# Radio_RPIZero.net
KiCad netlist of a schematic drawn in EAGLE
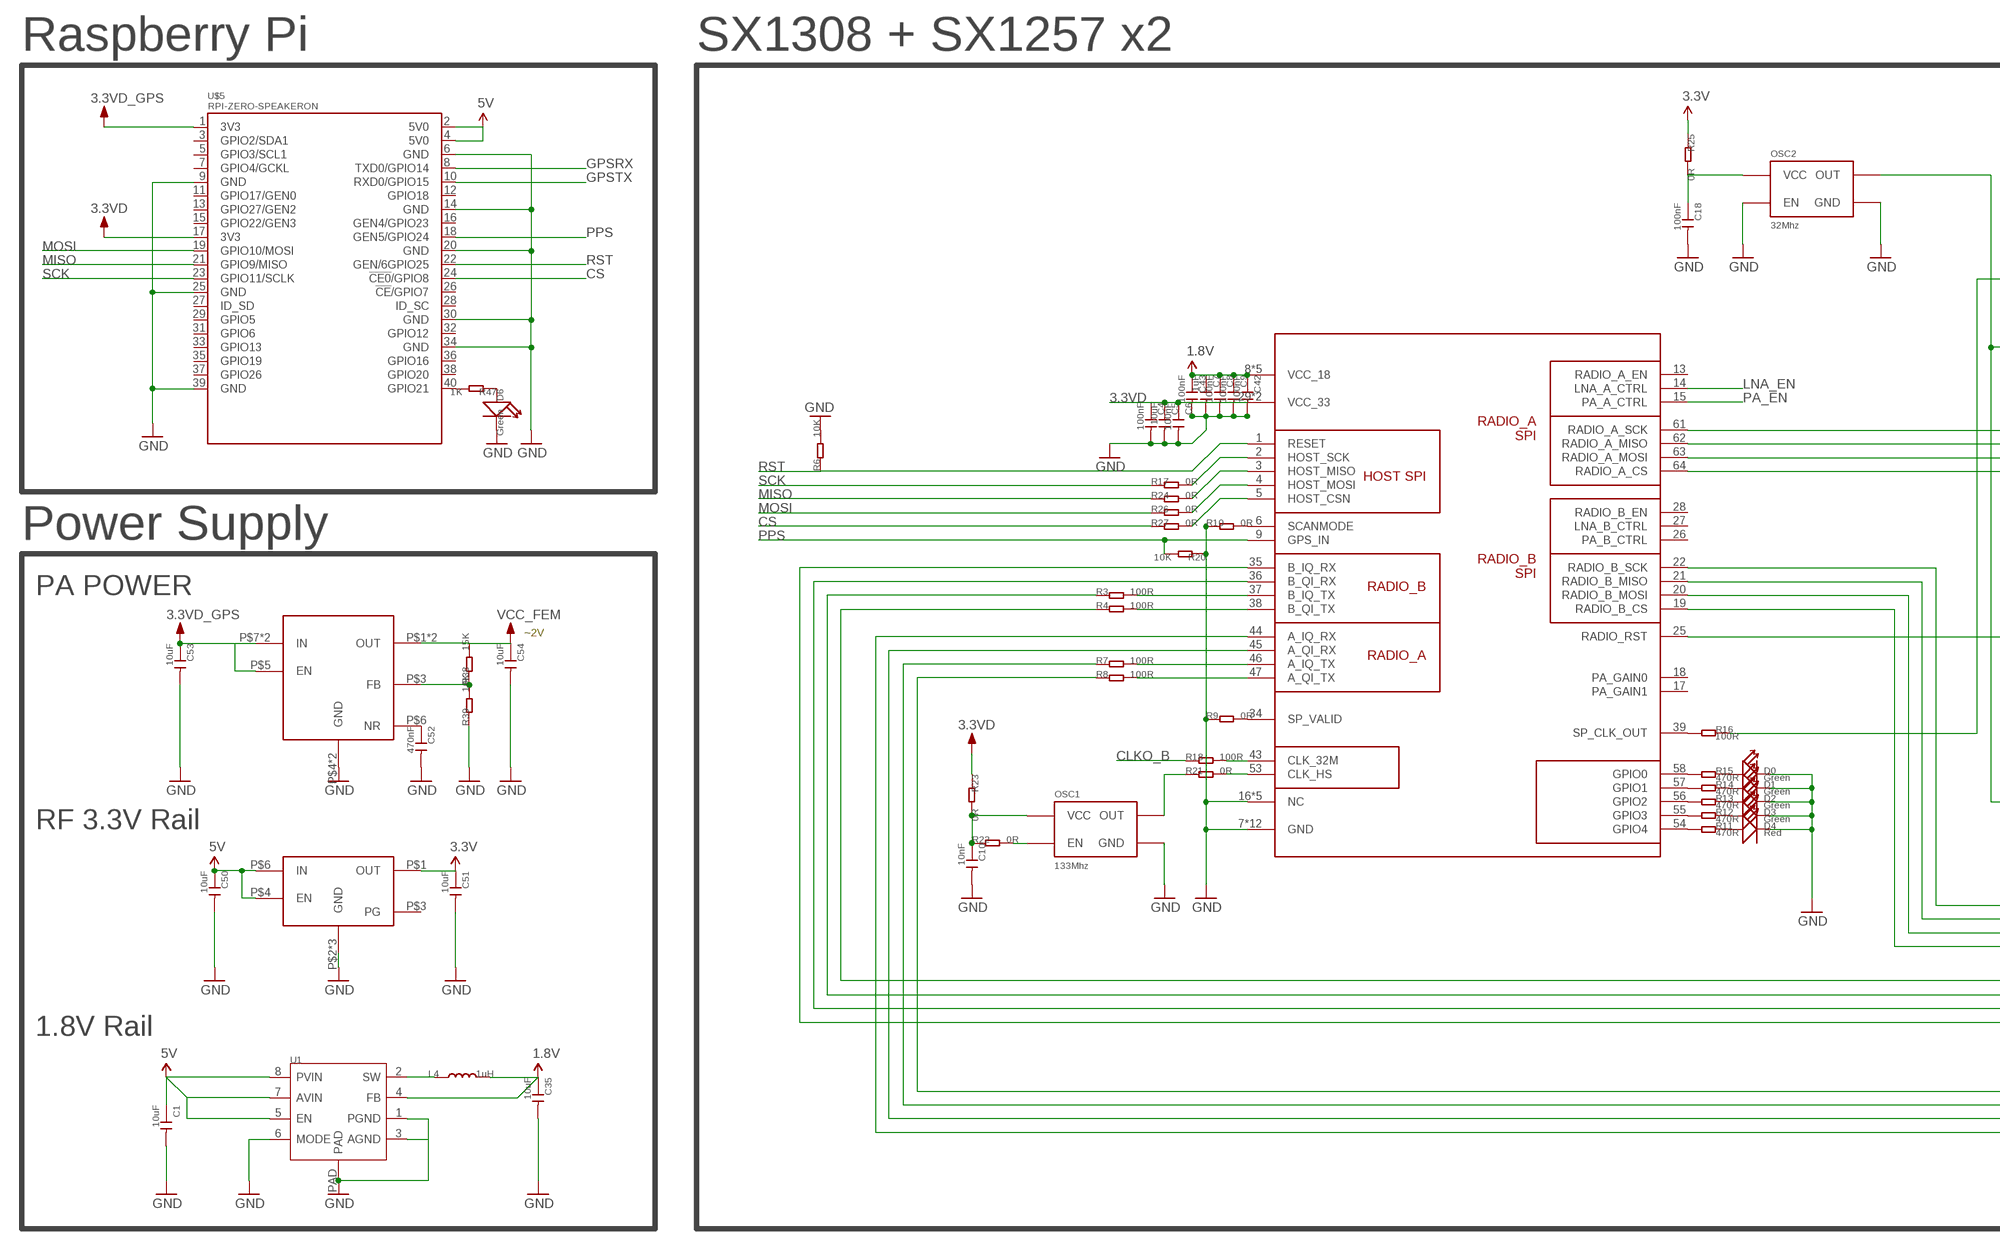
[diagram p0: schematic, sheet 1, part 1 of 2]
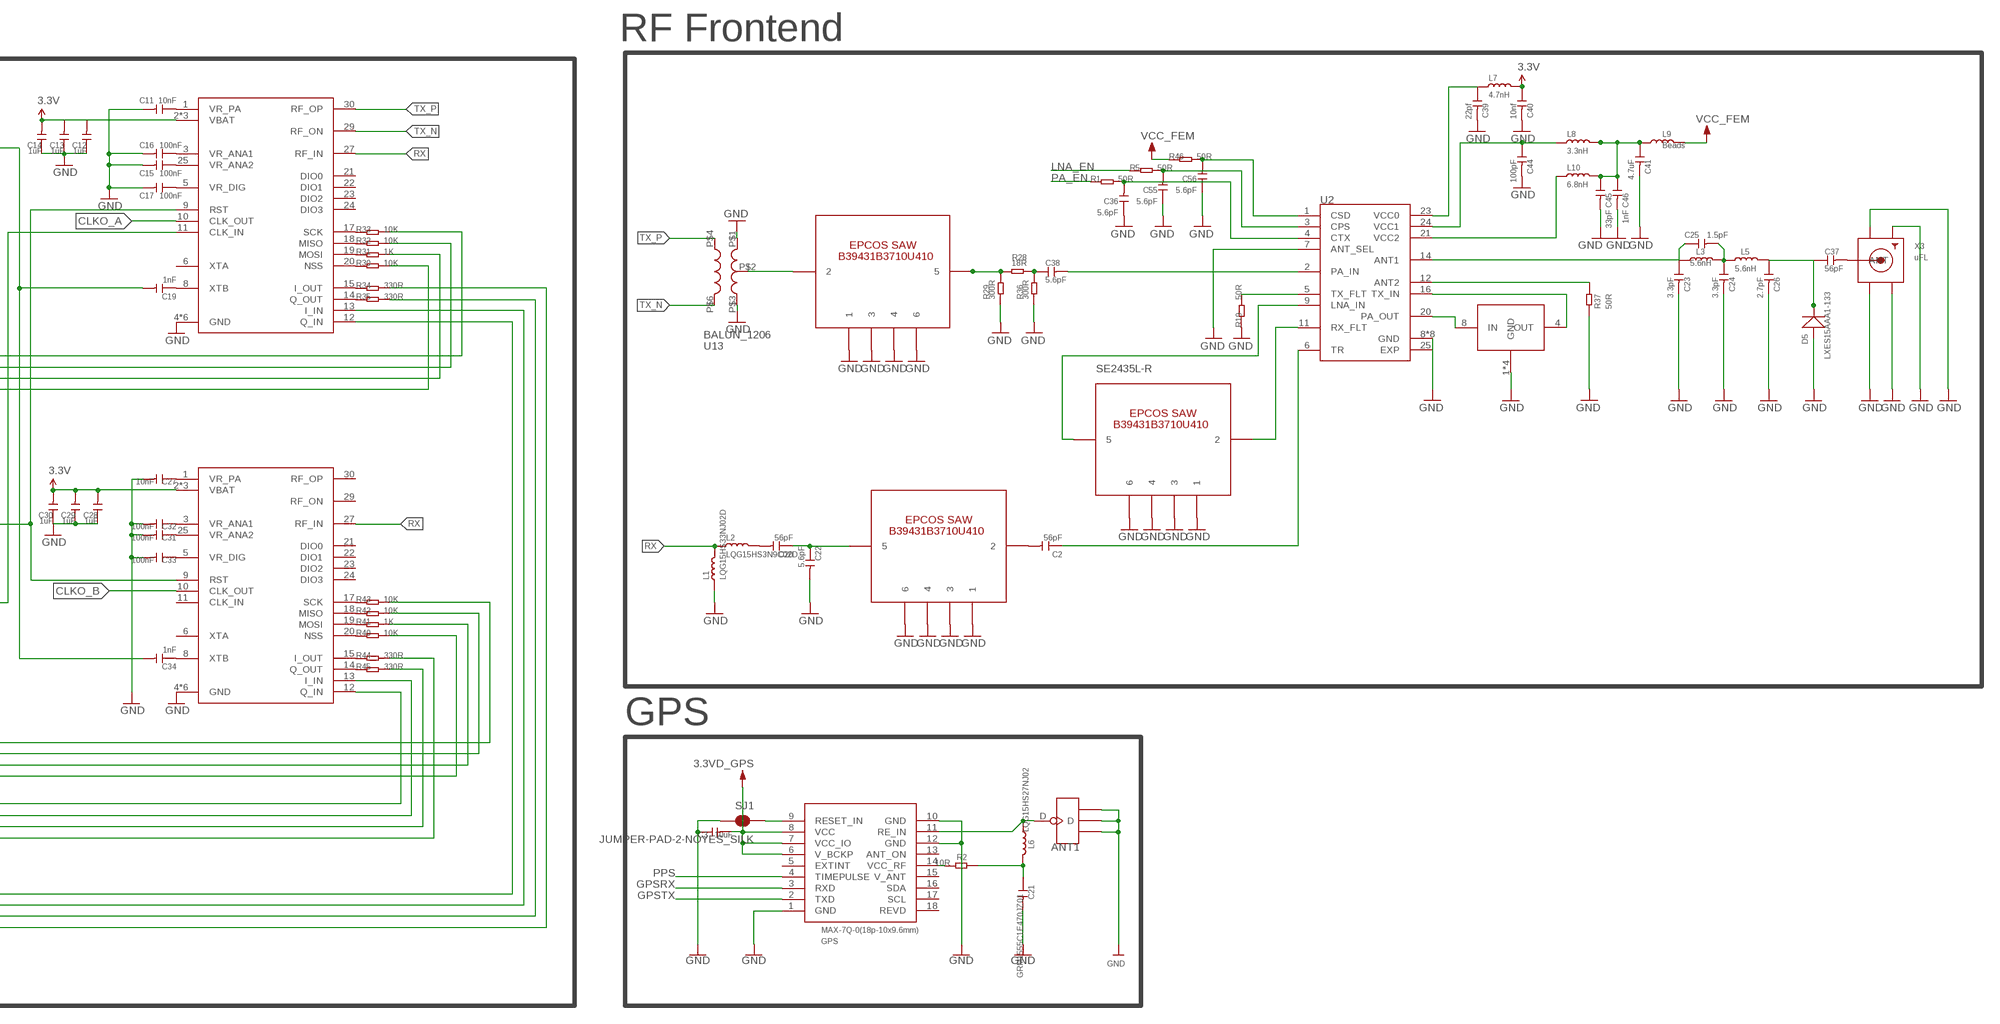
[diagram p1: schematic, sheet 1, part 2 of 2]

(export (version "E")
  (design (tool "Eeschema 10.0.6"))
  (components
    (comp (ref "ANT1")
      (value "ANTENNA-U-FL")
      (footprint "eagle-import:4P-U-FL")
      (libsource (lib "eagle-import") (part "ANTENNA-U-FL"))
    )
    (comp (ref "C1")
      (value "10uF")
      (footprint "eagle-import:C0603@1")
      (libsource (lib "eagle-import") (part "CAP-0603"))
    )
    (comp (ref "C2")
      (value "56pF")
      (footprint "eagle-import:C0402@1")
      (libsource (lib "eagle-import") (part "CAP-0402"))
    )
    (comp (ref "C3")
      (value "10uF")
      (footprint "eagle-import:C0603")
      (libsource (lib "eagle-import") (part "C-0603"))
    )
    (comp (ref "C4")
      (value "100nF")
      (footprint "eagle-import:C0402@1")
      (libsource (lib "eagle-import") (part "CAP-0402"))
    )
    (comp (ref "C5")
      (value "10uF")
      (footprint "eagle-import:C0402@1")
      (libsource (lib "eagle-import") (part "CAP-0402"))
    )
    (comp (ref "C6")
      (value "100nF")
      (footprint "eagle-import:C0402@1")
      (libsource (lib "eagle-import") (part "CAP-0402"))
    )
    (comp (ref "C7")
      (value "1uF")
      (footprint "eagle-import:C0402@1")
      (libsource (lib "eagle-import") (part "CAP-0402"))
    )
    (comp (ref "C8")
      (value "100nF")
      (footprint "eagle-import:C0402@1")
      (libsource (lib "eagle-import") (part "CAP-0402"))
    )
    (comp (ref "C9")
      (value "100nF")
      (footprint "eagle-import:C0402@1")
      (libsource (lib "eagle-import") (part "CAP-0402"))
    )
    (comp (ref "C10")
      (value "10nF")
      (footprint "eagle-import:C0402@1")
      (libsource (lib "eagle-import") (part "CAP-0402"))
    )
    (comp (ref "C11")
      (value "10nF")
      (footprint "eagle-import:C0402@1")
      (libsource (lib "eagle-import") (part "CAP-0402"))
    )
    (comp (ref "C12")
      (value "1uF")
      (footprint "eagle-import:C0402@1")
      (libsource (lib "eagle-import") (part "CAP-0402"))
    )
    (comp (ref "C13")
      (value "1uF")
      (footprint "eagle-import:C0402@1")
      (libsource (lib "eagle-import") (part "CAP-0402"))
    )
    (comp (ref "C14")
      (value "1uF")
      (footprint "eagle-import:C0402@1")
      (libsource (lib "eagle-import") (part "CAP-0402"))
    )
    (comp (ref "C15")
      (value "100nF")
      (footprint "eagle-import:C0402@1")
      (libsource (lib "eagle-import") (part "CAP-0402"))
    )
    (comp (ref "C16")
      (value "100nF")
      (footprint "eagle-import:C0402@1")
      (libsource (lib "eagle-import") (part "CAP-0402"))
    )
    (comp (ref "C17")
      (value "100nF")
      (footprint "eagle-import:C0402@1")
      (libsource (lib "eagle-import") (part "CAP-0402"))
    )
    (comp (ref "C18")
      (value "100nF")
      (footprint "eagle-import:C0402@1")
      (libsource (lib "eagle-import") (part "CAP-0402"))
    )
    (comp (ref "C19")
      (value "1nF")
      (footprint "eagle-import:C0402@1")
      (libsource (lib "eagle-import") (part "CAP-0402"))
    )
    (comp (ref "C20")
      (value "56pF")
      (footprint "eagle-import:C0402@1")
      (libsource (lib "eagle-import") (part "CAP-0402"))
    )
    (comp (ref "C21")
      (value "GRM1555C1E470JZ01")
      (footprint "eagle-import:C0402")
      (libsource (lib "eagle-import") (part "C-0402"))
    )
    (comp (ref "C22")
      (value "5.6pF")
      (footprint "eagle-import:C0402@1")
      (libsource (lib "eagle-import") (part "CAP-0402"))
    )
    (comp (ref "C23")
      (value "3.3pF")
      (footprint "eagle-import:C0402@1")
      (libsource (lib "eagle-import") (part "CAP-0402"))
    )
    (comp (ref "C24")
      (value "3.3pF")
      (footprint "eagle-import:C0402@1")
      (libsource (lib "eagle-import") (part "CAP-0402"))
    )
    (comp (ref "C25")
      (value "1.5pF")
      (footprint "eagle-import:C0402@1")
      (libsource (lib "eagle-import") (part "CAP-0402"))
    )
    (comp (ref "C26")
      (value "2.7pF")
      (footprint "eagle-import:C0402@1")
      (libsource (lib "eagle-import") (part "CAP-0402"))
    )
    (comp (ref "C27")
      (value "10nF")
      (footprint "eagle-import:C0402@1")
      (libsource (lib "eagle-import") (part "CAP-0402"))
    )
    (comp (ref "C28")
      (value "1uF")
      (footprint "eagle-import:C0402@1")
      (libsource (lib "eagle-import") (part "CAP-0402"))
    )
    (comp (ref "C29")
      (value "1uF")
      (footprint "eagle-import:C0402@1")
      (libsource (lib "eagle-import") (part "CAP-0402"))
    )
    (comp (ref "C30")
      (value "1uF")
      (footprint "eagle-import:C0402@1")
      (libsource (lib "eagle-import") (part "CAP-0402"))
    )
    (comp (ref "C31")
      (value "100nF")
      (footprint "eagle-import:C0402@1")
      (libsource (lib "eagle-import") (part "CAP-0402"))
    )
    (comp (ref "C32")
      (value "100nF")
      (footprint "eagle-import:C0402@1")
      (libsource (lib "eagle-import") (part "CAP-0402"))
    )
    (comp (ref "C33")
      (value "100nF")
      (footprint "eagle-import:C0402@1")
      (libsource (lib "eagle-import") (part "CAP-0402"))
    )
    (comp (ref "C34")
      (value "1nF")
      (footprint "eagle-import:C0402@1")
      (libsource (lib "eagle-import") (part "CAP-0402"))
    )
    (comp (ref "C35")
      (value "10uF")
      (footprint "eagle-import:C0603@1")
      (libsource (lib "eagle-import") (part "CAP-0603"))
    )
    (comp (ref "C36")
      (value "5.6pF")
      (footprint "eagle-import:C0402@1")
      (libsource (lib "eagle-import") (part "CAP-0402"))
    )
    (comp (ref "C37")
      (value "56pF")
      (footprint "eagle-import:C0402@1")
      (libsource (lib "eagle-import") (part "CAP-0402"))
    )
    (comp (ref "C38")
      (value "5.6pF")
      (footprint "eagle-import:C0402@1")
      (libsource (lib "eagle-import") (part "CAP-0402"))
    )
    (comp (ref "C39")
      (value "22pf")
      (footprint "eagle-import:C0402@1")
      (libsource (lib "eagle-import") (part "CAP-0402"))
    )
    (comp (ref "C40")
      (value "10nf")
      (footprint "eagle-import:C0402@1")
      (libsource (lib "eagle-import") (part "CAP-0402"))
    )
    (comp (ref "C41")
      (value "4.7uF")
      (footprint "eagle-import:C0402@1")
      (libsource (lib "eagle-import") (part "CAP-0402"))
    )
    (comp (ref "C42")
      (value "100nF")
      (footprint "eagle-import:C0402@1")
      (libsource (lib "eagle-import") (part "CAP-0402"))
    )
    (comp (ref "C43")
      (value "100nF")
      (footprint "eagle-import:C0402@1")
      (libsource (lib "eagle-import") (part "CAP-0402"))
    )
    (comp (ref "C44")
      (value "100pF")
      (footprint "eagle-import:C0402@1")
      (libsource (lib "eagle-import") (part "CAP-0402"))
    )
    (comp (ref "C45")
      (value "33pF")
      (footprint "eagle-import:C0402@1")
      (libsource (lib "eagle-import") (part "CAP-0402"))
    )
    (comp (ref "C46")
      (value "1nF")
      (footprint "eagle-import:C0402@1")
      (libsource (lib "eagle-import") (part "CAP-0402"))
    )
    (comp (ref "C50")
      (value "10uF")
      (footprint "eagle-import:C0603@1")
      (libsource (lib "eagle-import") (part "CAP-0603"))
    )
    (comp (ref "C51")
      (value "10uF")
      (footprint "eagle-import:C0603@1")
      (libsource (lib "eagle-import") (part "CAP-0603"))
    )
    (comp (ref "C52")
      (value "470nF")
      (footprint "eagle-import:C0402@1")
      (libsource (lib "eagle-import") (part "CAP-0402"))
    )
    (comp (ref "C53")
      (value "10uF")
      (footprint "eagle-import:C0402@1")
      (libsource (lib "eagle-import") (part "CAP-0402"))
    )
    (comp (ref "C54")
      (value "10uF")
      (footprint "eagle-import:C0402@1")
      (libsource (lib "eagle-import") (part "CAP-0402"))
    )
    (comp (ref "C55")
      (value "5.6pF")
      (footprint "eagle-import:C0402@1")
      (libsource (lib "eagle-import") (part "CAP-0402"))
    )
    (comp (ref "C56")
      (value "5.6pF")
      (footprint "eagle-import:C0402@1")
      (libsource (lib "eagle-import") (part "CAP-0402"))
    )
    (comp (ref "D0")
      (value "Green")
      (footprint "eagle-import:LED-0603@1")
      (libsource (lib "eagle-import") (part "LED-0603"))
    )
    (comp (ref "D1")
      (value "Green")
      (footprint "eagle-import:LED-0603@1")
      (libsource (lib "eagle-import") (part "LED-0603"))
    )
    (comp (ref "D2")
      (value "Green")
      (footprint "eagle-import:LED-0603@1")
      (libsource (lib "eagle-import") (part "LED-0603"))
    )
    (comp (ref "D3")
      (value "Green")
      (footprint "eagle-import:LED-0603@1")
      (libsource (lib "eagle-import") (part "LED-0603"))
    )
    (comp (ref "D4")
      (value "Red")
      (footprint "eagle-import:LED-0603@1")
      (libsource (lib "eagle-import") (part "LED-0603"))
    )
    (comp (ref "D5")
      (value "LXES15AAA1-133")
      (footprint "eagle-import:C0402")
      (libsource (lib "eagle-import") (part "D"))
    )
    (comp (ref "D6")
      (value "Green")
      (footprint "eagle-import:LED-0603")
      (libsource (lib "eagle-import") (part "LED'0603'"))
    )
    (comp (ref "GPS")
      (value "MAX-7Q-0(18p-10x9.6mm)")
      (footprint "eagle-import:GPS18P-SMD-1.1-10X9.6MM")
      (fields (field (name "MPN") "MAX-7Q-0"))
      (libsource (lib "eagle-import") (part "MODULE-GPS-SMD-MAX-7Q-0(18P-9.6X10MM)"))
    )
    (comp (ref "L1")
      (value "LQG15HS33NJ02D")
      (footprint "eagle-import:L0402@1")
      (libsource (lib "eagle-import") (part "INDUCTOR/FERRITE-BEAD-0402"))
    )
    (comp (ref "L2")
      (value "LQG15HS3N9C02D")
      (footprint "eagle-import:L0402@1")
      (libsource (lib "eagle-import") (part "INDUCTOR/FERRITE-BEAD-0402"))
    )
    (comp (ref "L3")
      (value "5.6nH")
      (footprint "eagle-import:L0402@1")
      (libsource (lib "eagle-import") (part "INDUCTOR/FERRITE-BEAD-0402"))
    )
    (comp (ref "L4")
      (value "1uH")
      (footprint "eagle-import:1616BZ")
      (libsource (lib "eagle-import") (part "L'1616BZ'"))
    )
    (comp (ref "L5")
      (value "5.6nH")
      (footprint "eagle-import:L0402@1")
      (libsource (lib "eagle-import") (part "INDUCTOR/FERRITE-BEAD-0402"))
    )
    (comp (ref "L6")
      (value "LQG15HS27NJ02")
      (footprint "eagle-import:L0402")
      (libsource (lib "eagle-import") (part "L'0402'"))
    )
    (comp (ref "L7")
      (value "4.7nH")
      (footprint "eagle-import:L0402@1")
      (libsource (lib "eagle-import") (part "INDUCTOR/FERRITE-BEAD-0402"))
    )
    (comp (ref "L8")
      (value "3.3nH")
      (footprint "eagle-import:L0402@1")
      (libsource (lib "eagle-import") (part "INDUCTOR/FERRITE-BEAD-0402"))
    )
    (comp (ref "L9")
      (value "Beads")
      (footprint "eagle-import:L0402@1")
      (libsource (lib "eagle-import") (part "INDUCTOR/FERRITE-BEAD-0402"))
    )
    (comp (ref "L10")
      (value "6.8nH")
      (footprint "eagle-import:L0402@1")
      (libsource (lib "eagle-import") (part "INDUCTOR/FERRITE-BEAD-0402"))
    )
    (comp (ref "OSC1")
      (value "133Mhz")
      (footprint "eagle-import:CRYSTAL-OSC-SMD-2.0X2.5")
      (libsource (lib "eagle-import") (part "OSCILLATOR3225"))
    )
    (comp (ref "OSC2")
      (value "32Mhz")
      (footprint "eagle-import:CRYSTAL-OSC-SMD-3.2X2.5")
      (libsource (lib "eagle-import") (part "OSCILLATOR"))
    )
    (comp (ref "R1")
      (value "50R")
      (footprint "eagle-import:R0402")
      (libsource (lib "eagle-import") (part "R-0402"))
    )
    (comp (ref "R2")
      (value "10R")
      (footprint "eagle-import:R0402")
      (libsource (lib "eagle-import") (part "R-0402"))
    )
    (comp (ref "R3")
      (value "100R")
      (footprint "eagle-import:R0402")
      (libsource (lib "eagle-import") (part "R-0402"))
    )
    (comp (ref "R4")
      (value "100R")
      (footprint "eagle-import:R0402")
      (libsource (lib "eagle-import") (part "R-0402"))
    )
    (comp (ref "R5")
      (value "50R")
      (footprint "eagle-import:R0402")
      (libsource (lib "eagle-import") (part "R-0402"))
    )
    (comp (ref "R6")
      (value "10K")
      (footprint "eagle-import:R0402")
      (libsource (lib "eagle-import") (part "R-0402"))
    )
    (comp (ref "R7")
      (value "100R")
      (footprint "eagle-import:R0402")
      (libsource (lib "eagle-import") (part "R-0402"))
    )
    (comp (ref "R8")
      (value "100R")
      (footprint "eagle-import:R0402")
      (libsource (lib "eagle-import") (part "R-0402"))
    )
    (comp (ref "R9")
      (value "0R")
      (footprint "eagle-import:R0402")
      (libsource (lib "eagle-import") (part "R-0402"))
    )
    (comp (ref "R10")
      (value "0R")
      (footprint "eagle-import:R0402")
      (libsource (lib "eagle-import") (part "R-0402"))
    )
    (comp (ref "R11")
      (value "470R")
      (footprint "eagle-import:R0402")
      (libsource (lib "eagle-import") (part "R-0402"))
    )
    (comp (ref "R12")
      (value "470R")
      (footprint "eagle-import:R0402")
      (libsource (lib "eagle-import") (part "R-0402"))
    )
    (comp (ref "R13")
      (value "470R")
      (footprint "eagle-import:R0402")
      (libsource (lib "eagle-import") (part "R-0402"))
    )
    (comp (ref "R14")
      (value "470R")
      (footprint "eagle-import:R0402")
      (libsource (lib "eagle-import") (part "R-0402"))
    )
    (comp (ref "R15")
      (value "470R")
      (footprint "eagle-import:R0402")
      (libsource (lib "eagle-import") (part "R-0402"))
    )
    (comp (ref "R16")
      (value "100R")
      (footprint "eagle-import:R0402")
      (libsource (lib "eagle-import") (part "R-0402"))
    )
    (comp (ref "R17")
      (value "0R")
      (footprint "eagle-import:R0402")
      (libsource (lib "eagle-import") (part "R-0402"))
    )
    (comp (ref "R18")
      (value "100R")
      (footprint "eagle-import:R0402")
      (libsource (lib "eagle-import") (part "R-0402"))
    )
    (comp (ref "R19")
      (value "50R")
      (footprint "eagle-import:R0402")
      (libsource (lib "eagle-import") (part "R-0402"))
    )
    (comp (ref "R20")
      (value "10K")
      (footprint "eagle-import:R0402")
      (libsource (lib "eagle-import") (part "R-0402"))
    )
    (comp (ref "R21")
      (value "0R")
      (footprint "eagle-import:R0402")
      (libsource (lib "eagle-import") (part "R-0402"))
    )
    (comp (ref "R22")
      (value "0R")
      (footprint "eagle-import:R0402")
      (libsource (lib "eagle-import") (part "R-0402"))
    )
    (comp (ref "R23")
      (value "0R")
      (footprint "eagle-import:R0402")
      (libsource (lib "eagle-import") (part "R-0402"))
    )
    (comp (ref "R24")
      (value "0R")
      (footprint "eagle-import:R0402")
      (libsource (lib "eagle-import") (part "R-0402"))
    )
    (comp (ref "R25")
      (value "0R")
      (footprint "eagle-import:R0402")
      (libsource (lib "eagle-import") (part "R-0402"))
    )
    (comp (ref "R26")
      (value "0R")
      (footprint "eagle-import:R0402")
      (libsource (lib "eagle-import") (part "R-0402"))
    )
    (comp (ref "R27")
      (value "0R")
      (footprint "eagle-import:R0402")
      (libsource (lib "eagle-import") (part "R-0402"))
    )
    (comp (ref "R28")
      (value "18R")
      (footprint "eagle-import:R0402")
      (libsource (lib "eagle-import") (part "R-0402"))
    )
    (comp (ref "R29")
      (value "300R")
      (footprint "eagle-import:R0402")
      (libsource (lib "eagle-import") (part "R-0402"))
    )
    (comp (ref "R30")
      (value "10K")
      (footprint "eagle-import:R0402")
      (libsource (lib "eagle-import") (part "R-0402"))
    )
    (comp (ref "R31")
      (value "1K")
      (footprint "eagle-import:R0402")
      (libsource (lib "eagle-import") (part "R-0402"))
    )
    (comp (ref "R32")
      (value "10K")
      (footprint "eagle-import:R0402")
      (libsource (lib "eagle-import") (part "R-0402"))
    )
    (comp (ref "R33")
      (value "10K")
      (footprint "eagle-import:R0402")
      (libsource (lib "eagle-import") (part "R-0402"))
    )
    (comp (ref "R34")
      (value "330R")
      (footprint "eagle-import:R0402")
      (libsource (lib "eagle-import") (part "R-0402"))
    )
    (comp (ref "R35")
      (value "330R")
      (footprint "eagle-import:R0402")
      (libsource (lib "eagle-import") (part "R-0402"))
    )
    (comp (ref "R36")
      (value "300R")
      (footprint "eagle-import:R0402")
      (libsource (lib "eagle-import") (part "R-0402"))
    )
    (comp (ref "R37")
      (value "50R")
      (footprint "eagle-import:R0402")
      (libsource (lib "eagle-import") (part "R-0402"))
    )
    (comp (ref "R38")
      (value "15K")
      (footprint "eagle-import:R0402")
      (libsource (lib "eagle-import") (part "R-0402"))
    )
    (comp (ref "R39")
      (value "10K")
      (footprint "eagle-import:R0402")
      (libsource (lib "eagle-import") (part "R-0402"))
    )
    (comp (ref "R40")
      (value "10K")
      (footprint "eagle-import:R0402")
      (libsource (lib "eagle-import") (part "R-0402"))
    )
    (comp (ref "R41")
      (value "1K")
      (footprint "eagle-import:R0402")
      (libsource (lib "eagle-import") (part "R-0402"))
    )
    (comp (ref "R42")
      (value "10K")
      (footprint "eagle-import:R0402")
      (libsource (lib "eagle-import") (part "R-0402"))
    )
    (comp (ref "R43")
      (value "10K")
      (footprint "eagle-import:R0402")
      (libsource (lib "eagle-import") (part "R-0402"))
    )
    (comp (ref "R44")
      (value "330R")
      (footprint "eagle-import:R0402")
      (libsource (lib "eagle-import") (part "R-0402"))
    )
    (comp (ref "R45")
      (value "330R")
      (footprint "eagle-import:R0402")
      (libsource (lib "eagle-import") (part "R-0402"))
    )
    (comp (ref "R46")
      (value "50R")
      (footprint "eagle-import:R0402")
      (libsource (lib "eagle-import") (part "R-0402"))
    )
    (comp (ref "R47")
      (value "1K")
      (footprint "eagle-import:R0402")
      (libsource (lib "eagle-import") (part "R-0402"))
    )
    (comp (ref "SJ1")
      (value "JUMPER-PAD-2-NOYES_SILK")
      (footprint "eagle-import:PAD-JUMPER-2-NO_YES_SILK")
      (libsource (lib "eagle-import") (part "JUMPER-PAD-2-NOYES_SILK"))
    )
    (comp (ref "U$1")
      (value "SX1301")
      (footprint "eagle-import:QFN64G-0.5-9X9MM")
      (libsource (lib "eagle-import") (part "SX1301"))
    )
    (comp (ref "U$2")
      (value "SX1255")
      (footprint "eagle-import:QFN32G-0.5-5X5MM")
      (libsource (lib "eagle-import") (part "SX1255"))
    )
    (comp (ref "U$3")
      (value "SX1255")
      (footprint "eagle-import:QFN32G-0.5-5X5MM")
      (libsource (lib "eagle-import") (part "SX1255"))
    )
    (comp (ref "U$4")
      (value "B39921B3728U410")
      (footprint "eagle-import:EPCOS_SAW_FILTER")
      (libsource (lib "eagle-import") (part "EPCOS_SAW_FILTER"))
    )
    (comp (ref "U$5")
      (value "RPI-ZERO-SPEAKERON")
      (footprint "eagle-import:RASPBERRYPI_BASTELSTUBE_V13_RASPI_BOARD_B+_FULL")
      (libsource (lib "eagle-import") (part "RPI-ZERO-SPEAKERON"))
    )
    (comp (ref "U$6")
      (value "LP5912")
      (footprint "eagle-import:WSON6")
      (libsource (lib "eagle-import") (part "LP5912"))
    )
    (comp (ref "U$7")
      (value "B39921B3728U410")
      (footprint "eagle-import:EPCOS_SAW_FILTER")
      (libsource (lib "eagle-import") (part "EPCOS_SAW_FILTER"))
    )
    (comp (ref "U$8")
      (value "B39921B3728U410")
      (footprint "eagle-import:EPCOS_SAW_FILTER")
      (libsource (lib "eagle-import") (part "EPCOS_SAW_FILTER"))
    )
    (comp (ref "U$9")
      (value "TPS7A8101")
      (footprint "eagle-import:VSON8")
      (libsource (lib "eagle-import") (part "TPS7A8101"))
    )
    (comp (ref "U$10")
      (value "0915LP15B026")
      (footprint "eagle-import:0915LP15B026")
      (libsource (lib "eagle-import") (part "0915LP15B026"))
    )
    (comp (ref "U1")
      (value "PMIC-ETA3410D2I-T(DFN8-2X2)WSON")
      (footprint "eagle-import:WSON")
      (libsource (lib "eagle-import") (part "PMIC-ETA3410D2I-T(DFN8-2X2)WSON"))
    )
    (comp (ref "U2")
      (value "SE2435L-R")
      (footprint "eagle-import:QFN50P400X400X90-25N")
      (fields (field (name "DIGI-KEY_PART_NUMBER") "863-1349-1-ND") (field (name "MF") "Skyworks Solutions"))
      (libsource (lib "eagle-import") (part "SE2435L-R"))
    )
    (comp (ref "U13")
      (value "BALUN_1206")
      (footprint "eagle-import:BALUN_1206")
      (libsource (lib "eagle-import") (part "BALUN_1206"))
    )
    (comp (ref "X3")
      (value "uFL")
      (footprint "eagle-import:SMA_EDGELAUNCH_UFL")
      (libsource (lib "eagle-import") (part "SMACONNECTOR_EDGE_UFL"))
    )
  )
  (nets
    (net (code "1") (name "/CS") (class "Default")
      (node (ref "R27") (pin "1") (pinfunction "1_1") (pintype "passive"))
      (node (ref "U$5") (pin "24") (pinfunction "~{CE0}/GPIO8_24") (pintype "bidirectional"))
    )
    (net (code "2") (name "/GPSRX") (class "Default")
      (node (ref "GPS") (pin "3") (pinfunction "RXD_3") (pintype "bidirectional"))
      (node (ref "U$5") (pin "8") (pinfunction "TXD0/GPIO14_8") (pintype "bidirectional"))
    )
    (net (code "3") (name "/GPSTX") (class "Default")
      (node (ref "GPS") (pin "2") (pinfunction "TXD_2") (pintype "bidirectional"))
      (node (ref "U$5") (pin "10") (pinfunction "RXD0/GPIO15_10") (pintype "bidirectional"))
    )
    (net (code "4") (name "/LNA_EN") (class "Default")
      (node (ref "R5") (pin "1") (pinfunction "1_1") (pintype "passive"))
      (node (ref "U$1") (pin "14") (pinfunction "LNA_A_CTRL_14") (pintype "bidirectional"))
    )
    (net (code "5") (name "/MISO") (class "Default")
      (node (ref "R24") (pin "1") (pinfunction "1_1") (pintype "passive"))
      (node (ref "U$5") (pin "21") (pinfunction "GPIO9/MISO_21") (pintype "bidirectional"))
    )
    (net (code "6") (name "/MOSI") (class "Default")
      (node (ref "R26") (pin "1") (pinfunction "1_1") (pintype "passive"))
      (node (ref "U$5") (pin "19") (pinfunction "GPIO10/MOSI_19") (pintype "bidirectional"))
    )
    (net (code "7") (name "/PA_EN") (class "Default")
      (node (ref "R1") (pin "1") (pinfunction "1_1") (pintype "passive"))
      (node (ref "U$1") (pin "15") (pinfunction "PA_A_CTRL_15") (pintype "bidirectional"))
    )
    (net (code "8") (name "/PPS") (class "Default")
      (node (ref "GPS") (pin "4") (pinfunction "TIMEPULSE_4") (pintype "bidirectional"))
      (node (ref "R20") (pin "2") (pinfunction "2_2") (pintype "passive"))
      (node (ref "U$1") (pin "9") (pinfunction "GPS_IN_9") (pintype "bidirectional"))
      (node (ref "U$5") (pin "18") (pinfunction "GEN5/GPIO24_18") (pintype "bidirectional"))
    )
    (net (code "9") (name "/RST") (class "Default")
      (node (ref "R6") (pin "1") (pinfunction "1_1") (pintype "passive"))
      (node (ref "U$1") (pin "1") (pinfunction "RESET_1") (pintype "bidirectional"))
      (node (ref "U$5") (pin "22") (pinfunction "GEN/6GPIO25_22") (pintype "bidirectional"))
    )
    (net (code "10") (name "/SCK") (class "Default")
      (node (ref "R17") (pin "1") (pinfunction "1_1") (pintype "passive"))
      (node (ref "U$5") (pin "23") (pinfunction "GPIO11/SCLK_23") (pintype "bidirectional"))
    )
    (net (code "11") (name "1.8V") (class "Default")
      (node (ref "C35") (pin "1") (pinfunction "1_1") (pintype "passive"))
      (node (ref "C42") (pin "1") (pinfunction "1_1") (pintype "passive"))
      (node (ref "C43") (pin "1") (pinfunction "1_1") (pintype "passive"))
      (node (ref "C7") (pin "1") (pinfunction "1_1") (pintype "passive"))
      (node (ref "C8") (pin "1") (pinfunction "1_1") (pintype "passive"))
      (node (ref "C9") (pin "1") (pinfunction "1_1") (pintype "passive"))
      (node (ref "L4") (pin "2") (pinfunction "2_2") (pintype "passive"))
      (node (ref "U$1") (pin "12") (pinfunction "VCC_18_12") (pintype "bidirectional"))
      (node (ref "U$1") (pin "23") (pinfunction "VCC_18_23") (pintype "bidirectional"))
      (node (ref "U$1") (pin "42") (pinfunction "VCC_18_42") (pintype "bidirectional"))
      (node (ref "U$1") (pin "60") (pinfunction "VCC_18_60") (pintype "bidirectional"))
      (node (ref "U$1") (pin "8") (pinfunction "VCC_18_8") (pintype "bidirectional"))
      (node (ref "U1") (pin "4") (pinfunction "FB_4") (pintype "bidirectional"))
    )
    (net (code "12") (name "3.3V") (class "Default")
      (node (ref "C12") (pin "2") (pinfunction "2_2") (pintype "passive"))
      (node (ref "C13") (pin "2") (pinfunction "2_2") (pintype "passive"))
      (node (ref "C14") (pin "2") (pinfunction "2_2") (pintype "passive"))
      (node (ref "C28") (pin "2") (pinfunction "2_2") (pintype "passive"))
      (node (ref "C29") (pin "2") (pinfunction "2_2") (pintype "passive"))
      (node (ref "C30") (pin "2") (pinfunction "2_2") (pintype "passive"))
      (node (ref "C40") (pin "1") (pinfunction "1_1") (pintype "passive"))
      (node (ref "C51") (pin "1") (pinfunction "1_1") (pintype "passive"))
      (node (ref "L7") (pin "2") (pinfunction "2_2") (pintype "passive"))
      (node (ref "R25") (pin "1") (pinfunction "1_1") (pintype "passive"))
      (node (ref "U$2") (pin "16") (pinfunction "VBAT_16") (pintype "bidirectional"))
      (node (ref "U$2") (pin "2") (pinfunction "VBAT_2") (pintype "bidirectional"))
      (node (ref "U$2") (pin "32") (pinfunction "VBAT_32") (pintype "bidirectional"))
      (node (ref "U$3") (pin "16") (pinfunction "VBAT_16") (pintype "bidirectional"))
      (node (ref "U$3") (pin "2") (pinfunction "VBAT_2") (pintype "bidirectional"))
      (node (ref "U$3") (pin "32") (pinfunction "VBAT_32") (pintype "bidirectional"))
      (node (ref "U$6") (pin "P$1") (pinfunction "OUT_P$1") (pintype "bidirectional"))
    )
    (net (code "13") (name "3.3VD") (class "Default")
      (node (ref "C4") (pin "1") (pinfunction "1_1") (pintype "passive"))
      (node (ref "C5") (pin "1") (pinfunction "1_1") (pintype "passive"))
      (node (ref "C6") (pin "1") (pinfunction "1_1") (pintype "passive"))
      (node (ref "R23") (pin "1") (pinfunction "1_1") (pintype "passive"))
      (node (ref "U$1") (pin "29") (pinfunction "VCC_33_29") (pintype "bidirectional"))
      (node (ref "U$1") (pin "52") (pinfunction "VCC_33_52") (pintype "bidirectional"))
      (node (ref "U$5") (pin "17") (pinfunction "3V3_17") (pintype "power_in"))
    )
    (net (code "14") (name "3.3VD_GPS") (class "Default")
      (node (ref "C3") (pin "2") (pinfunction "2_2") (pintype "passive"))
      (node (ref "C53") (pin "1") (pinfunction "1_1") (pintype "passive"))
      (node (ref "GPS") (pin "6") (pinfunction "V_BCKP_6") (pintype "bidirectional"))
      (node (ref "GPS") (pin "7") (pinfunction "VCC_IO_7") (pintype "bidirectional"))
      (node (ref "GPS") (pin "8") (pinfunction "VCC_8") (pintype "bidirectional"))
      (node (ref "U$5") (pin "1") (pinfunction "3V3_1") (pintype "power_in"))
      (node (ref "U$9") (pin "P$5") (pinfunction "EN_P$5") (pintype "bidirectional"))
      (node (ref "U$9") (pin "P$7") (pinfunction "IN_P$7") (pintype "bidirectional"))
      (node (ref "U$9") (pin "P$8") (pinfunction "IN_P$8") (pintype "bidirectional"))
    )
    (net (code "15") (name "5V") (class "Default")
      (node (ref "C1") (pin "1") (pinfunction "1_1") (pintype "passive"))
      (node (ref "C50") (pin "1") (pinfunction "1_1") (pintype "passive"))
      (node (ref "U$5") (pin "2") (pinfunction "5V0_2") (pintype "power_in"))
      (node (ref "U$5") (pin "4") (pinfunction "5V0_4") (pintype "power_in"))
      (node (ref "U$6") (pin "P$4") (pinfunction "EN_P$4") (pintype "bidirectional"))
      (node (ref "U$6") (pin "P$6") (pinfunction "IN_P$6") (pintype "bidirectional"))
      (node (ref "U1") (pin "5") (pinfunction "EN_5") (pintype "bidirectional"))
      (node (ref "U1") (pin "7") (pinfunction "AVIN_7") (pintype "bidirectional"))
      (node (ref "U1") (pin "8") (pinfunction "PVIN_8") (pintype "bidirectional"))
    )
    (net (code "16") (name "CLKO_A") (class "Default")
      (node (ref "U$2") (pin "10") (pinfunction "CLK_OUT_10") (pintype "bidirectional"))
    )
    (net (code "17") (name "CLKO_B") (class "Default")
      (node (ref "R18") (pin "1") (pinfunction "1_1") (pintype "passive"))
      (node (ref "U$3") (pin "10") (pinfunction "CLK_OUT_10") (pintype "bidirectional"))
    )
    (net (code "18") (name "GND") (class "Default")
      (node (ref "ANT1") (pin "GND1") (pinfunction "GND1_GND1") (pintype "bidirectional"))
      (node (ref "ANT1") (pin "GND2") (pinfunction "GND2_GND2") (pintype "bidirectional"))
      (node (ref "ANT1") (pin "GND3") (pinfunction "GND3_GND3") (pintype "bidirectional"))
      (node (ref "C1") (pin "2") (pinfunction "2_2") (pintype "passive"))
      (node (ref "C10") (pin "2") (pinfunction "2_2") (pintype "passive"))
      (node (ref "C11") (pin "2") (pinfunction "2_2") (pintype "passive"))
      (node (ref "C12") (pin "1") (pinfunction "1_1") (pintype "passive"))
      (node (ref "C13") (pin "1") (pinfunction "1_1") (pintype "passive"))
      (node (ref "C14") (pin "1") (pinfunction "1_1") (pintype "passive"))
      (node (ref "C15") (pin "2") (pinfunction "2_2") (pintype "passive"))
      (node (ref "C16") (pin "2") (pinfunction "2_2") (pintype "passive"))
      (node (ref "C17") (pin "2") (pinfunction "2_2") (pintype "passive"))
      (node (ref "C18") (pin "2") (pinfunction "2_2") (pintype "passive"))
      (node (ref "C21") (pin "2") (pinfunction "2_2") (pintype "passive"))
      (node (ref "C22") (pin "2") (pinfunction "2_2") (pintype "passive"))
      (node (ref "C23") (pin "2") (pinfunction "2_2") (pintype "passive"))
      (node (ref "C24") (pin "2") (pinfunction "2_2") (pintype "passive"))
      (node (ref "C26") (pin "2") (pinfunction "2_2") (pintype "passive"))
      (node (ref "C27") (pin "2") (pinfunction "2_2") (pintype "passive"))
      (node (ref "C28") (pin "1") (pinfunction "1_1") (pintype "passive"))
      (node (ref "C29") (pin "1") (pinfunction "1_1") (pintype "passive"))
      (node (ref "C3") (pin "1") (pinfunction "1_1") (pintype "passive"))
      (node (ref "C30") (pin "1") (pinfunction "1_1") (pintype "passive"))
      (node (ref "C31") (pin "2") (pinfunction "2_2") (pintype "passive"))
      (node (ref "C32") (pin "2") (pinfunction "2_2") (pintype "passive"))
      (node (ref "C33") (pin "2") (pinfunction "2_2") (pintype "passive"))
      (node (ref "C35") (pin "2") (pinfunction "2_2") (pintype "passive"))
      (node (ref "C36") (pin "1") (pinfunction "1_1") (pintype "passive"))
      (node (ref "C39") (pin "2") (pinfunction "2_2") (pintype "passive"))
      (node (ref "C4") (pin "2") (pinfunction "2_2") (pintype "passive"))
      (node (ref "C40") (pin "2") (pinfunction "2_2") (pintype "passive"))
      (node (ref "C41") (pin "2") (pinfunction "2_2") (pintype "passive"))
      (node (ref "C42") (pin "2") (pinfunction "2_2") (pintype "passive"))
      (node (ref "C43") (pin "2") (pinfunction "2_2") (pintype "passive"))
      (node (ref "C44") (pin "2") (pinfunction "2_2") (pintype "passive"))
      (node (ref "C45") (pin "2") (pinfunction "2_2") (pintype "passive"))
      (node (ref "C46") (pin "2") (pinfunction "2_2") (pintype "passive"))
      (node (ref "C5") (pin "2") (pinfunction "2_2") (pintype "passive"))
      (node (ref "C50") (pin "2") (pinfunction "2_2") (pintype "passive"))
      (node (ref "C51") (pin "2") (pinfunction "2_2") (pintype "passive"))
      (node (ref "C52") (pin "2") (pinfunction "2_2") (pintype "passive"))
      (node (ref "C53") (pin "2") (pinfunction "2_2") (pintype "passive"))
      (node (ref "C54") (pin "2") (pinfunction "2_2") (pintype "passive"))
      (node (ref "C55") (pin "1") (pinfunction "1_1") (pintype "passive"))
      (node (ref "C56") (pin "1") (pinfunction "1_1") (pintype "passive"))
      (node (ref "C6") (pin "2") (pinfunction "2_2") (pintype "passive"))
      (node (ref "C7") (pin "2") (pinfunction "2_2") (pintype "passive"))
      (node (ref "C8") (pin "2") (pinfunction "2_2") (pintype "passive"))
      (node (ref "C9") (pin "2") (pinfunction "2_2") (pintype "passive"))
      (node (ref "D0") (pin "-") (pinfunction "-_-") (pintype "passive"))
      (node (ref "D1") (pin "-") (pinfunction "-_-") (pintype "passive"))
      (node (ref "D2") (pin "-") (pinfunction "-_-") (pintype "passive"))
      (node (ref "D3") (pin "-") (pinfunction "-_-") (pintype "passive"))
      (node (ref "D4") (pin "-") (pinfunction "-_-") (pintype "passive"))
      (node (ref "D5") (pin "1") (pinfunction "+_1") (pintype "passive"))
      (node (ref "D6") (pin "-") (pinfunction "-_-") (pintype "passive"))
      (node (ref "GPS") (pin "1") (pinfunction "GND_1") (pintype "bidirectional"))
      (node (ref "GPS") (pin "10") (pinfunction "GND_10") (pintype "bidirectional"))
      (node (ref "GPS") (pin "12") (pinfunction "GND_12") (pintype "bidirectional"))
      (node (ref "L1") (pin "1") (pinfunction "1_1") (pintype "passive"))
      (node (ref "OSC1") (pin "2") (pinfunction "GND_2") (pintype "bidirectional"))
      (node (ref "OSC2") (pin "P$1") (pinfunction "EN_P$1") (pintype "bidirectional"))
      (node (ref "OSC2") (pin "P$2") (pinfunction "GND_P$2") (pintype "bidirectional"))
      (node (ref "R10") (pin "1") (pinfunction "1_1") (pintype "passive"))
      (node (ref "R19") (pin "1") (pinfunction "1_1") (pintype "passive"))
      (node (ref "R20") (pin "1") (pinfunction "1_1") (pintype "passive"))
      (node (ref "R29") (pin "1") (pinfunction "1_1") (pintype "passive"))
      (node (ref "R36") (pin "1") (pinfunction "1_1") (pintype "passive"))
      (node (ref "R37") (pin "2") (pinfunction "2_2") (pintype "passive"))
      (node (ref "R39") (pin "1") (pinfunction "1_1") (pintype "passive"))
      (node (ref "R6") (pin "2") (pinfunction "2_2") (pintype "passive"))
      (node (ref "R9") (pin "1") (pinfunction "1_1") (pintype "passive"))
      (node (ref "SJ1") (pin "2") (pinfunction "2_2") (pintype "passive"))
      (node (ref "U$1") (pin "10") (pinfunction "GND_10") (pintype "bidirectional"))
      (node (ref "U$1") (pin "11") (pinfunction "GND_11") (pintype "bidirectional"))
      (node (ref "U$1") (pin "16") (pinfunction "NC_16") (pintype "bidirectional"))
      (node (ref "U$1") (pin "24") (pinfunction "GND_24") (pintype "bidirectional"))
      (node (ref "U$1") (pin "30") (pinfunction "GND_30") (pintype "bidirectional"))
      (node (ref "U$1") (pin "31") (pinfunction "GND_31") (pintype "bidirectional"))
      (node (ref "U$1") (pin "32") (pinfunction "NC_32") (pintype "bidirectional"))
      (node (ref "U$1") (pin "33") (pinfunction "NC_33") (pintype "bidirectional"))
      (node (ref "U$1") (pin "40") (pinfunction "GND_40") (pintype "bidirectional"))
      (node (ref "U$1") (pin "41") (pinfunction "GND_41") (pintype "bidirectional"))
      (node (ref "U$1") (pin "48") (pinfunction "NC_48") (pintype "bidirectional"))
      (node (ref "U$1") (pin "49") (pinfunction "NC_49") (pintype "bidirectional"))
      (node (ref "U$1") (pin "50") (pinfunction "GND_50") (pintype "bidirectional"))
      (node (ref "U$1") (pin "51") (pinfunction "GND_51") (pintype "bidirectional"))
      (node (ref "U$1") (pin "59") (pinfunction "GND_59") (pintype "bidirectional"))
      (node (ref "U$1") (pin "65") (pinfunction "GND_65") (pintype "bidirectional"))
      (node (ref "U$1") (pin "7") (pinfunction "GND_7") (pintype "bidirectional"))
      (node (ref "U$10") (pin "1") (pinfunction "GND_1") (pintype "bidirectional"))
      (node (ref "U$10") (pin "3") (pinfunction "GND_3") (pintype "bidirectional"))
      (node (ref "U$10") (pin "5") (pinfunction "GND_5") (pintype "bidirectional"))
      (node (ref "U$10") (pin "7") (pinfunction "GND_7") (pintype "bidirectional"))
      (node (ref "U$2") (pin "26") (pinfunction "GND_26") (pintype "bidirectional"))
      (node (ref "U$2") (pin "28") (pinfunction "GND_28") (pintype "bidirectional"))
      (node (ref "U$2") (pin "31") (pinfunction "GND_31") (pintype "bidirectional"))
      (node (ref "U$2") (pin "33") (pinfunction "GND_33") (pintype "bidirectional"))
      (node (ref "U$2") (pin "4") (pinfunction "GND_4") (pintype "bidirectional"))
      (node (ref "U$2") (pin "7") (pinfunction "GND_7") (pintype "bidirectional"))
      (node (ref "U$3") (pin "26") (pinfunction "GND_26") (pintype "bidirectional"))
      (node (ref "U$3") (pin "28") (pinfunction "GND_28") (pintype "bidirectional"))
      (node (ref "U$3") (pin "31") (pinfunction "GND_31") (pintype "bidirectional"))
      (node (ref "U$3") (pin "33") (pinfunction "GND_33") (pintype "bidirectional"))
      (node (ref "U$3") (pin "4") (pinfunction "GND_4") (pintype "bidirectional"))
      (node (ref "U$3") (pin "7") (pinfunction "GND_7") (pintype "bidirectional"))
      (node (ref "U$4") (pin "P$1") (pinfunction "1_P$1") (pintype "bidirectional"))
      (node (ref "U$4") (pin "P$3") (pinfunction "3_P$3") (pintype "bidirectional"))
      (node (ref "U$4") (pin "P$4") (pinfunction "4_P$4") (pintype "bidirectional"))
      (node (ref "U$4") (pin "P$6") (pinfunction "6_P$6") (pintype "bidirectional"))
      (node (ref "U$5") (pin "14") (pinfunction "GND_14") (pintype "power_in"))
      (node (ref "U$5") (pin "20") (pinfunction "GND_20") (pintype "power_in"))
      (node (ref "U$5") (pin "25") (pinfunction "GND_25") (pintype "power_in"))
      (node (ref "U$5") (pin "30") (pinfunction "GND_30") (pintype "power_in"))
      (node (ref "U$5") (pin "34") (pinfunction "GND_34") (pintype "power_in"))
      (node (ref "U$5") (pin "39") (pinfunction "GND_39") (pintype "power_in"))
      (node (ref "U$5") (pin "6") (pinfunction "GND_6") (pintype "power_in"))
      (node (ref "U$5") (pin "9") (pinfunction "GND_9") (pintype "power_in"))
      (node (ref "U$6") (pin "P$2") (pinfunction "GND_P$2") (pintype "bidirectional"))
      (node (ref "U$6") (pin "P$5") (pinfunction "GND_P$5") (pintype "bidirectional"))
      (node (ref "U$6") (pin "PAD") (pinfunction "GND_PAD") (pintype "bidirectional"))
      (node (ref "U$7") (pin "P$1") (pinfunction "1_P$1") (pintype "bidirectional"))
      (node (ref "U$7") (pin "P$3") (pinfunction "3_P$3") (pintype "bidirectional"))
      (node (ref "U$7") (pin "P$4") (pinfunction "4_P$4") (pintype "bidirectional"))
      (node (ref "U$7") (pin "P$6") (pinfunction "6_P$6") (pintype "bidirectional"))
      (node (ref "U$8") (pin "P$1") (pinfunction "1_P$1") (pintype "bidirectional"))
      (node (ref "U$8") (pin "P$3") (pinfunction "3_P$3") (pintype "bidirectional"))
      (node (ref "U$8") (pin "P$4") (pinfunction "4_P$4") (pintype "bidirectional"))
      (node (ref "U$8") (pin "P$6") (pinfunction "6_P$6") (pintype "bidirectional"))
      (node (ref "U$9") (pin "P$4") (pinfunction "GND_P$4") (pintype "bidirectional"))
      (node (ref "U$9") (pin "PAD") (pinfunction "GND_PAD") (pintype "bidirectional"))
      (node (ref "U1") (pin "1") (pinfunction "PGND_1") (pintype "bidirectional"))
      (node (ref "U1") (pin "3") (pinfunction "AGND_3") (pintype "bidirectional"))
      (node (ref "U1") (pin "6") (pinfunction "MODE_6") (pintype "bidirectional"))
      (node (ref "U1") (pin "PAD") (pinfunction "PAD_PAD") (pintype "bidirectional"))
      (node (ref "U13") (pin "P$1") (pinfunction "GND_1_P$1") (pintype "bidirectional"))
      (node (ref "U13") (pin "P$3") (pinfunction "GND_2_P$3") (pintype "bidirectional"))
      (node (ref "U2") (pin "10") (pinfunction "GND_10") (pintype "power_in"))
      (node (ref "U2") (pin "13") (pinfunction "GND_13") (pintype "power_in"))
      (node (ref "U2") (pin "15") (pinfunction "GND_15") (pintype "power_in"))
      (node (ref "U2") (pin "17") (pinfunction "GND_17") (pintype "power_in"))
      (node (ref "U2") (pin "18") (pinfunction "GND_18") (pintype "power_in"))
      (node (ref "U2") (pin "19") (pinfunction "GND_19") (pintype "power_in"))
      (node (ref "U2") (pin "22") (pinfunction "GND_22") (pintype "power_in"))
      (node (ref "U2") (pin "25") (pinfunction "EXP_25") (pintype "power_in"))
      (node (ref "U2") (pin "7") (pinfunction "ANT_SEL_7") (pintype "input"))
      (node (ref "U2") (pin "8") (pinfunction "GND_8") (pintype "power_in"))
      (node (ref "X3") (pin "GND@1") (pinfunction "GND1_GND@1") (pintype "power_in"))
      (node (ref "X3") (pin "GND@2") (pinfunction "GND2_GND@2") (pintype "power_in"))
      (node (ref "X3") (pin "GND@3") (pinfunction "GND3_GND@3") (pintype "power_in"))
      (node (ref "X3") (pin "GND@4") (pinfunction "GND4_GND@4") (pintype "power_in"))
    )
    (net (code "19") (name "Net-(C20-Pad2)") (class "Default")
      (node (ref "C20") (pin "2") (pinfunction "2_2") (pintype "passive"))
      (node (ref "L2") (pin "2") (pinfunction "2_2") (pintype "passive"))
    )
    (net (code "20") (name "Net-(C21-Pad1)") (class "Default")
      (node (ref "C21") (pin "1") (pinfunction "1_1") (pintype "passive"))
      (node (ref "L6") (pin "1") (pinfunction "1_1") (pintype "passive"))
      (node (ref "R2") (pin "1") (pinfunction "1_1") (pintype "passive"))
    )
    (net (code "21") (name "Net-(C24-Pad1)") (class "Default")
      (node (ref "C24") (pin "1") (pinfunction "1_1") (pintype "passive"))
      (node (ref "C25") (pin "2") (pinfunction "2_2") (pintype "passive"))
      (node (ref "L3") (pin "2") (pinfunction "2_2") (pintype "passive"))
      (node (ref "L5") (pin "1") (pinfunction "1_1") (pintype "passive"))
    )
    (net (code "22") (name "Net-(C38-Pad1)") (class "Default")
      (node (ref "C38") (pin "1") (pinfunction "1_1") (pintype "passive"))
      (node (ref "R28") (pin "2") (pinfunction "2_2") (pintype "passive"))
      (node (ref "R36") (pin "2") (pinfunction "2_2") (pintype "passive"))
    )
    (net (code "23") (name "Net-(C41-Pad1)") (class "Default")
      (node (ref "C41") (pin "1") (pinfunction "1_1") (pintype "passive"))
      (node (ref "C45") (pin "1") (pinfunction "1_1") (pintype "passive"))
      (node (ref "C46") (pin "1") (pinfunction "1_1") (pintype "passive"))
      (node (ref "L10") (pin "2") (pinfunction "2_2") (pintype "passive"))
      (node (ref "L8") (pin "2") (pinfunction "2_2") (pintype "passive"))
      (node (ref "L9") (pin "1") (pinfunction "1_1") (pintype "passive"))
    )
    (net (code "24") (name "Net-(D0-Pad+)") (class "Default")
      (node (ref "D0") (pin "+") (pinfunction "+_+") (pintype "passive"))
      (node (ref "R15") (pin "2") (pinfunction "2_2") (pintype "passive"))
    )
    (net (code "25") (name "Net-(D1-Pad+)") (class "Default")
      (node (ref "D1") (pin "+") (pinfunction "+_+") (pintype "passive"))
      (node (ref "R14") (pin "2") (pinfunction "2_2") (pintype "passive"))
    )
    (net (code "26") (name "Net-(D2-Pad+)") (class "Default")
      (node (ref "D2") (pin "+") (pinfunction "+_+") (pintype "passive"))
      (node (ref "R13") (pin "2") (pinfunction "2_2") (pintype "passive"))
    )
    (net (code "27") (name "Net-(D3-Pad+)") (class "Default")
      (node (ref "D3") (pin "+") (pinfunction "+_+") (pintype "passive"))
      (node (ref "R12") (pin "2") (pinfunction "2_2") (pintype "passive"))
    )
    (net (code "28") (name "Net-(D4-Pad+)") (class "Default")
      (node (ref "D4") (pin "+") (pinfunction "+_+") (pintype "passive"))
      (node (ref "R11") (pin "2") (pinfunction "2_2") (pintype "passive"))
    )
    (net (code "29") (name "Net-(D5--)") (class "Default")
      (node (ref "C26") (pin "1") (pinfunction "1_1") (pintype "passive"))
      (node (ref "C37") (pin "1") (pinfunction "1_1") (pintype "passive"))
      (node (ref "D5") (pin "2") (pinfunction "-_2") (pintype "passive"))
      (node (ref "L5") (pin "2") (pinfunction "2_2") (pintype "passive"))
    )
    (net (code "30") (name "Net-(D6-Pad+)") (class "Default")
      (node (ref "D6") (pin "+") (pinfunction "+_+") (pintype "passive"))
      (node (ref "R47") (pin "1") (pinfunction "1_1") (pintype "passive"))
    )
    (net (code "31") (name "Net-(GPS-RESET_IN)") (class "Default")
      (node (ref "GPS") (pin "9") (pinfunction "RESET_IN_9") (pintype "bidirectional"))
      (node (ref "SJ1") (pin "1") (pinfunction "1_1") (pintype "passive"))
    )
    (net (code "32") (name "Net-(GPS-RE_IN)") (class "Default")
      (node (ref "ANT1") (pin "D") (pinfunction "D_D") (pintype "bidirectional"))
      (node (ref "GPS") (pin "11") (pinfunction "RE_IN_11") (pintype "bidirectional"))
      (node (ref "L6") (pin "2") (pinfunction "2_2") (pintype "passive"))
    )
    (net (code "33") (name "Net-(GPS-VCC_RF)") (class "Default")
      (node (ref "GPS") (pin "14") (pinfunction "VCC_RF_14") (pintype "bidirectional"))
      (node (ref "R2") (pin "2") (pinfunction "2_2") (pintype "passive"))
    )
    (net (code "34") (name "Net-(OSC1-EN)") (class "Default")
      (node (ref "OSC1") (pin "1") (pinfunction "EN_1") (pintype "bidirectional"))
      (node (ref "R22") (pin "2") (pinfunction "2_2") (pintype "passive"))
    )
    (net (code "35") (name "Net-(OSC1-OUT)") (class "Default")
      (node (ref "OSC1") (pin "3") (pinfunction "OUT_3") (pintype "bidirectional"))
      (node (ref "R21") (pin "1") (pinfunction "1_1") (pintype "passive"))
    )
    (net (code "36") (name "Net-(OSC1-VCC)") (class "Default")
      (node (ref "C10") (pin "1") (pinfunction "1_1") (pintype "passive"))
      (node (ref "OSC1") (pin "4") (pinfunction "VCC_4") (pintype "bidirectional"))
      (node (ref "R22") (pin "1") (pinfunction "1_1") (pintype "passive"))
      (node (ref "R23") (pin "2") (pinfunction "2_2") (pintype "passive"))
    )
    (net (code "37") (name "Net-(OSC2-OUT)") (class "Default")
      (node (ref "C19") (pin "2") (pinfunction "2_2") (pintype "passive"))
      (node (ref "C34") (pin "2") (pinfunction "2_2") (pintype "passive"))
      (node (ref "OSC2") (pin "P$3") (pinfunction "OUT_P$3") (pintype "bidirectional"))
    )
    (net (code "38") (name "Net-(OSC2-VCC)") (class "Default")
      (node (ref "C18") (pin "1") (pinfunction "1_1") (pintype "passive"))
      (node (ref "OSC2") (pin "P$4") (pinfunction "VCC_P$4") (pintype "bidirectional"))
      (node (ref "R25") (pin "2") (pinfunction "2_2") (pintype "passive"))
    )
    (net (code "39") (name "Net-(U$1-A_IQ_RX)") (class "Default")
      (node (ref "R34") (pin "2") (pinfunction "2_2") (pintype "passive"))
      (node (ref "U$1") (pin "44") (pinfunction "A_IQ_RX_44") (pintype "bidirectional"))
    )
    (net (code "40") (name "Net-(U$1-A_IQ_TX)") (class "Default")
      (node (ref "R7") (pin "2") (pinfunction "2_2") (pintype "passive"))
      (node (ref "U$1") (pin "46") (pinfunction "A_IQ_TX_46") (pintype "bidirectional"))
    )
    (net (code "41") (name "Net-(U$1-A_QI_RX)") (class "Default")
      (node (ref "R35") (pin "2") (pinfunction "2_2") (pintype "passive"))
      (node (ref "U$1") (pin "45") (pinfunction "A_QI_RX_45") (pintype "bidirectional"))
    )
    (net (code "42") (name "Net-(U$1-A_QI_TX)") (class "Default")
      (node (ref "R8") (pin "2") (pinfunction "2_2") (pintype "passive"))
      (node (ref "U$1") (pin "47") (pinfunction "A_QI_TX_47") (pintype "bidirectional"))
    )
    (net (code "43") (name "Net-(U$1-B_IQ_RX)") (class "Default")
      (node (ref "R44") (pin "2") (pinfunction "2_2") (pintype "passive"))
      (node (ref "U$1") (pin "35") (pinfunction "B_IQ_RX_35") (pintype "bidirectional"))
    )
    (net (code "44") (name "Net-(U$1-B_IQ_TX)") (class "Default")
      (node (ref "R3") (pin "2") (pinfunction "2_2") (pintype "passive"))
      (node (ref "U$1") (pin "37") (pinfunction "B_IQ_TX_37") (pintype "bidirectional"))
    )
    (net (code "45") (name "Net-(U$1-B_QI_RX)") (class "Default")
      (node (ref "R45") (pin "2") (pinfunction "2_2") (pintype "passive"))
      (node (ref "U$1") (pin "36") (pinfunction "B_QI_RX_36") (pintype "bidirectional"))
    )
    (net (code "46") (name "Net-(U$1-B_QI_TX)") (class "Default")
      (node (ref "R4") (pin "2") (pinfunction "2_2") (pintype "passive"))
      (node (ref "U$1") (pin "38") (pinfunction "B_QI_TX_38") (pintype "bidirectional"))
    )
    (net (code "47") (name "Net-(U$1-CLK_32M)") (class "Default")
      (node (ref "R18") (pin "2") (pinfunction "2_2") (pintype "passive"))
      (node (ref "U$1") (pin "43") (pinfunction "CLK_32M_43") (pintype "bidirectional"))
    )
    (net (code "48") (name "Net-(U$1-CLK_HS)") (class "Default")
      (node (ref "R21") (pin "2") (pinfunction "2_2") (pintype "passive"))
      (node (ref "U$1") (pin "53") (pinfunction "CLK_HS_53") (pintype "bidirectional"))
    )
    (net (code "49") (name "Net-(U$1-GPIO0)") (class "Default")
      (node (ref "R15") (pin "1") (pinfunction "1_1") (pintype "passive"))
      (node (ref "U$1") (pin "58") (pinfunction "GPIO0_58") (pintype "bidirectional"))
    )
    (net (code "50") (name "Net-(U$1-GPIO1)") (class "Default")
      (node (ref "R14") (pin "1") (pinfunction "1_1") (pintype "passive"))
      (node (ref "U$1") (pin "57") (pinfunction "GPIO1_57") (pintype "bidirectional"))
    )
    (net (code "51") (name "Net-(U$1-GPIO2)") (class "Default")
      (node (ref "R13") (pin "1") (pinfunction "1_1") (pintype "passive"))
      (node (ref "U$1") (pin "56") (pinfunction "GPIO2_56") (pintype "bidirectional"))
    )
    (net (code "52") (name "Net-(U$1-GPIO3)") (class "Default")
      (node (ref "R12") (pin "1") (pinfunction "1_1") (pintype "passive"))
      (node (ref "U$1") (pin "55") (pinfunction "GPIO3_55") (pintype "bidirectional"))
    )
    (net (code "53") (name "Net-(U$1-GPIO4)") (class "Default")
      (node (ref "R11") (pin "1") (pinfunction "1_1") (pintype "passive"))
      (node (ref "U$1") (pin "54") (pinfunction "GPIO4_54") (pintype "bidirectional"))
    )
    (net (code "54") (name "Net-(U$1-HOST_CSN)") (class "Default")
      (node (ref "R27") (pin "2") (pinfunction "2_2") (pintype "passive"))
      (node (ref "U$1") (pin "5") (pinfunction "HOST_CSN_5") (pintype "bidirectional"))
    )
    (net (code "55") (name "Net-(U$1-HOST_MISO)") (class "Default")
      (node (ref "R24") (pin "2") (pinfunction "2_2") (pintype "passive"))
      (node (ref "U$1") (pin "3") (pinfunction "HOST_MISO_3") (pintype "bidirectional"))
    )
    (net (code "56") (name "Net-(U$1-HOST_MOSI)") (class "Default")
      (node (ref "R26") (pin "2") (pinfunction "2_2") (pintype "passive"))
      (node (ref "U$1") (pin "4") (pinfunction "HOST_MOSI_4") (pintype "bidirectional"))
    )
    (net (code "57") (name "Net-(U$1-HOST_SCK)") (class "Default")
      (node (ref "R17") (pin "2") (pinfunction "2_2") (pintype "passive"))
      (node (ref "U$1") (pin "2") (pinfunction "HOST_SCK_2") (pintype "bidirectional"))
    )
    (net (code "58") (name "Net-(U$1-RADIO_A_CS)") (class "Default")
      (node (ref "R30") (pin "2") (pinfunction "2_2") (pintype "passive"))
      (node (ref "U$1") (pin "64") (pinfunction "RADIO_A_CS_64") (pintype "bidirectional"))
    )
    (net (code "59") (name "Net-(U$1-RADIO_A_MISO)") (class "Default")
      (node (ref "R32") (pin "2") (pinfunction "2_2") (pintype "passive"))
      (node (ref "U$1") (pin "62") (pinfunction "RADIO_A_MISO_62") (pintype "bidirectional"))
    )
    (net (code "60") (name "Net-(U$1-RADIO_A_MOSI)") (class "Default")
      (node (ref "R31") (pin "2") (pinfunction "2_2") (pintype "passive"))
      (node (ref "U$1") (pin "63") (pinfunction "RADIO_A_MOSI_63") (pintype "bidirectional"))
    )
    (net (code "61") (name "Net-(U$1-RADIO_A_SCK)") (class "Default")
      (node (ref "R33") (pin "2") (pinfunction "2_2") (pintype "passive"))
      (node (ref "U$1") (pin "61") (pinfunction "RADIO_A_SCK_61") (pintype "bidirectional"))
    )
    (net (code "62") (name "Net-(U$1-RADIO_B_CS)") (class "Default")
      (node (ref "R40") (pin "2") (pinfunction "2_2") (pintype "passive"))
      (node (ref "U$1") (pin "19") (pinfunction "RADIO_B_CS_19") (pintype "bidirectional"))
    )
    (net (code "63") (name "Net-(U$1-RADIO_B_MISO)") (class "Default")
      (node (ref "R42") (pin "2") (pinfunction "2_2") (pintype "passive"))
      (node (ref "U$1") (pin "21") (pinfunction "RADIO_B_MISO_21") (pintype "bidirectional"))
    )
    (net (code "64") (name "Net-(U$1-RADIO_B_MOSI)") (class "Default")
      (node (ref "R41") (pin "2") (pinfunction "2_2") (pintype "passive"))
      (node (ref "U$1") (pin "20") (pinfunction "RADIO_B_MOSI_20") (pintype "bidirectional"))
    )
    (net (code "65") (name "Net-(U$1-RADIO_B_SCK)") (class "Default")
      (node (ref "R43") (pin "2") (pinfunction "2_2") (pintype "passive"))
      (node (ref "U$1") (pin "22") (pinfunction "RADIO_B_SCK_22") (pintype "bidirectional"))
    )
    (net (code "66") (name "Net-(U$1-RADIO_RST)") (class "Default")
      (node (ref "U$1") (pin "25") (pinfunction "RADIO_RST_25") (pintype "bidirectional"))
      (node (ref "U$2") (pin "9") (pinfunction "RST_9") (pintype "bidirectional"))
      (node (ref "U$3") (pin "9") (pinfunction "RST_9") (pintype "bidirectional"))
    )
    (net (code "67") (name "Net-(U$1-SCANMODE)") (class "Default")
      (node (ref "R10") (pin "2") (pinfunction "2_2") (pintype "passive"))
      (node (ref "U$1") (pin "6") (pinfunction "SCANMODE_6") (pintype "bidirectional"))
    )
    (net (code "68") (name "Net-(U$1-SP_CLK_OUT)") (class "Default")
      (node (ref "R16") (pin "1") (pinfunction "1_1") (pintype "passive"))
      (node (ref "U$1") (pin "39") (pinfunction "SP_CLK_OUT_39") (pintype "bidirectional"))
    )
    (net (code "69") (name "Net-(U$1-SP_VALID)") (class "Default")
      (node (ref "R9") (pin "2") (pinfunction "2_2") (pintype "passive"))
      (node (ref "U$1") (pin "34") (pinfunction "SP_VALID_34") (pintype "bidirectional"))
    )
    (net (code "70") (name "Net-(U$2-CLK_IN)") (class "Default")
      (node (ref "R16") (pin "2") (pinfunction "2_2") (pintype "passive"))
      (node (ref "U$2") (pin "11") (pinfunction "CLK_IN_11") (pintype "bidirectional"))
    )
    (net (code "71") (name "Net-(U$2-I_IN)") (class "Default")
      (node (ref "R7") (pin "1") (pinfunction "1_1") (pintype "passive"))
      (node (ref "U$2") (pin "13") (pinfunction "I_IN_13") (pintype "bidirectional"))
    )
    (net (code "72") (name "Net-(U$2-I_OUT)") (class "Default")
      (node (ref "R34") (pin "1") (pinfunction "1_1") (pintype "passive"))
      (node (ref "U$2") (pin "15") (pinfunction "I_OUT_15") (pintype "bidirectional"))
    )
    (net (code "73") (name "Net-(U$2-MISO)") (class "Default")
      (node (ref "R32") (pin "1") (pinfunction "1_1") (pintype "passive"))
      (node (ref "U$2") (pin "18") (pinfunction "MISO_18") (pintype "bidirectional"))
    )
    (net (code "74") (name "Net-(U$2-MOSI)") (class "Default")
      (node (ref "R31") (pin "1") (pinfunction "1_1") (pintype "passive"))
      (node (ref "U$2") (pin "19") (pinfunction "MOSI_19") (pintype "bidirectional"))
    )
    (net (code "75") (name "Net-(U$2-NSS)") (class "Default")
      (node (ref "R30") (pin "1") (pinfunction "1_1") (pintype "passive"))
      (node (ref "U$2") (pin "20") (pinfunction "NSS_20") (pintype "bidirectional"))
    )
    (net (code "76") (name "Net-(U$2-Q_IN)") (class "Default")
      (node (ref "R8") (pin "1") (pinfunction "1_1") (pintype "passive"))
      (node (ref "U$2") (pin "12") (pinfunction "Q_IN_12") (pintype "bidirectional"))
    )
    (net (code "77") (name "Net-(U$2-Q_OUT)") (class "Default")
      (node (ref "R35") (pin "1") (pinfunction "1_1") (pintype "passive"))
      (node (ref "U$2") (pin "14") (pinfunction "Q_OUT_14") (pintype "bidirectional"))
    )
    (net (code "78") (name "Net-(U$2-SCK)") (class "Default")
      (node (ref "R33") (pin "1") (pinfunction "1_1") (pintype "passive"))
      (node (ref "U$2") (pin "17") (pinfunction "SCK_17") (pintype "bidirectional"))
    )
    (net (code "79") (name "Net-(U$2-VR_ANA1)") (class "Default")
      (node (ref "C16") (pin "1") (pinfunction "1_1") (pintype "passive"))
      (node (ref "U$2") (pin "3") (pinfunction "VR_ANA1_3") (pintype "bidirectional"))
    )
    (net (code "80") (name "Net-(U$2-VR_ANA2)") (class "Default")
      (node (ref "C15") (pin "1") (pinfunction "1_1") (pintype "passive"))
      (node (ref "U$2") (pin "25") (pinfunction "VR_ANA2_25") (pintype "bidirectional"))
    )
    (net (code "81") (name "Net-(U$2-VR_DIG)") (class "Default")
      (node (ref "C17") (pin "1") (pinfunction "1_1") (pintype "passive"))
      (node (ref "U$2") (pin "5") (pinfunction "VR_DIG_5") (pintype "bidirectional"))
    )
    (net (code "82") (name "Net-(U$2-VR_PA)") (class "Default")
      (node (ref "C11") (pin "1") (pinfunction "1_1") (pintype "passive"))
      (node (ref "U$2") (pin "1") (pinfunction "VR_PA_1") (pintype "bidirectional"))
    )
    (net (code "83") (name "Net-(U$2-XTB)") (class "Default")
      (node (ref "C19") (pin "1") (pinfunction "1_1") (pintype "passive"))
      (node (ref "U$2") (pin "8") (pinfunction "XTB_8") (pintype "bidirectional"))
    )
    (net (code "84") (name "Net-(U$3-I_IN)") (class "Default")
      (node (ref "R3") (pin "1") (pinfunction "1_1") (pintype "passive"))
      (node (ref "U$3") (pin "13") (pinfunction "I_IN_13") (pintype "bidirectional"))
    )
    (net (code "85") (name "Net-(U$3-I_OUT)") (class "Default")
      (node (ref "R44") (pin "1") (pinfunction "1_1") (pintype "passive"))
      (node (ref "U$3") (pin "15") (pinfunction "I_OUT_15") (pintype "bidirectional"))
    )
    (net (code "86") (name "Net-(U$3-MISO)") (class "Default")
      (node (ref "R42") (pin "1") (pinfunction "1_1") (pintype "passive"))
      (node (ref "U$3") (pin "18") (pinfunction "MISO_18") (pintype "bidirectional"))
    )
    (net (code "87") (name "Net-(U$3-MOSI)") (class "Default")
      (node (ref "R41") (pin "1") (pinfunction "1_1") (pintype "passive"))
      (node (ref "U$3") (pin "19") (pinfunction "MOSI_19") (pintype "bidirectional"))
    )
    (net (code "88") (name "Net-(U$3-NSS)") (class "Default")
      (node (ref "R40") (pin "1") (pinfunction "1_1") (pintype "passive"))
      (node (ref "U$3") (pin "20") (pinfunction "NSS_20") (pintype "bidirectional"))
    )
    (net (code "89") (name "Net-(U$3-Q_IN)") (class "Default")
      (node (ref "R4") (pin "1") (pinfunction "1_1") (pintype "passive"))
      (node (ref "U$3") (pin "12") (pinfunction "Q_IN_12") (pintype "bidirectional"))
    )
    (net (code "90") (name "Net-(U$3-Q_OUT)") (class "Default")
      (node (ref "R45") (pin "1") (pinfunction "1_1") (pintype "passive"))
      (node (ref "U$3") (pin "14") (pinfunction "Q_OUT_14") (pintype "bidirectional"))
    )
    (net (code "91") (name "Net-(U$3-SCK)") (class "Default")
      (node (ref "R43") (pin "1") (pinfunction "1_1") (pintype "passive"))
      (node (ref "U$3") (pin "17") (pinfunction "SCK_17") (pintype "bidirectional"))
    )
    (net (code "92") (name "Net-(U$3-VR_ANA1)") (class "Default")
      (node (ref "C32") (pin "1") (pinfunction "1_1") (pintype "passive"))
      (node (ref "U$3") (pin "3") (pinfunction "VR_ANA1_3") (pintype "bidirectional"))
    )
    (net (code "93") (name "Net-(U$3-VR_ANA2)") (class "Default")
      (node (ref "C31") (pin "1") (pinfunction "1_1") (pintype "passive"))
      (node (ref "U$3") (pin "25") (pinfunction "VR_ANA2_25") (pintype "bidirectional"))
    )
    (net (code "94") (name "Net-(U$3-VR_DIG)") (class "Default")
      (node (ref "C33") (pin "1") (pinfunction "1_1") (pintype "passive"))
      (node (ref "U$3") (pin "5") (pinfunction "VR_DIG_5") (pintype "bidirectional"))
    )
    (net (code "95") (name "Net-(U$3-VR_PA)") (class "Default")
      (node (ref "C27") (pin "1") (pinfunction "1_1") (pintype "passive"))
      (node (ref "U$3") (pin "1") (pinfunction "VR_PA_1") (pintype "bidirectional"))
    )
    (net (code "96") (name "Net-(U$3-XTB)") (class "Default")
      (node (ref "C34") (pin "1") (pinfunction "1_1") (pintype "passive"))
      (node (ref "U$3") (pin "8") (pinfunction "XTB_8") (pintype "bidirectional"))
    )
    (net (code "97") (name "Net-(U$4-2)") (class "Default")
      (node (ref "C2") (pin "2") (pinfunction "2_2") (pintype "passive"))
      (node (ref "U$4") (pin "P$2") (pinfunction "2_P$2") (pintype "bidirectional"))
    )
    (net (code "98") (name "Net-(U$4-5)") (class "Default")
      (node (ref "C20") (pin "1") (pinfunction "1_1") (pintype "passive"))
      (node (ref "C22") (pin "1") (pinfunction "1_1") (pintype "passive"))
      (node (ref "U$4") (pin "P$5") (pinfunction "5_P$5") (pintype "bidirectional"))
    )
    (net (code "99") (name "Net-(U$5-GPIO21)") (class "Default")
      (node (ref "R47") (pin "2") (pinfunction "2_2") (pintype "passive"))
      (node (ref "U$5") (pin "40") (pinfunction "GPIO21_40") (pintype "bidirectional"))
    )
    (net (code "100") (name "Net-(U$7-2)") (class "Default")
      (node (ref "U$7") (pin "P$2") (pinfunction "2_P$2") (pintype "bidirectional"))
      (node (ref "U13") (pin "P$2") (pinfunction "UNBALANCE_P$2") (pintype "bidirectional"))
    )
    (net (code "101") (name "Net-(U$7-5)") (class "Default")
      (node (ref "R28") (pin "1") (pinfunction "1_1") (pintype "passive"))
      (node (ref "R29") (pin "2") (pinfunction "2_2") (pintype "passive"))
      (node (ref "U$7") (pin "P$5") (pinfunction "5_P$5") (pintype "bidirectional"))
    )
    (net (code "102") (name "Net-(U$8-2)") (class "Default")
      (node (ref "U$8") (pin "P$2") (pinfunction "2_P$2") (pintype "bidirectional"))
      (node (ref "U2") (pin "11") (pinfunction "RX_FLT_11") (pintype "input"))
    )
    (net (code "103") (name "Net-(U$8-5)") (class "Default")
      (node (ref "U$8") (pin "P$5") (pinfunction "5_P$5") (pintype "bidirectional"))
      (node (ref "U2") (pin "9") (pinfunction "LNA_IN_9") (pintype "input"))
    )
    (net (code "104") (name "Net-(U$9-FB)") (class "Default")
      (node (ref "R38") (pin "1") (pinfunction "1_1") (pintype "passive"))
      (node (ref "R39") (pin "2") (pinfunction "2_2") (pintype "passive"))
      (node (ref "U$9") (pin "P$3") (pinfunction "FB_P$3") (pintype "bidirectional"))
    )
    (net (code "105") (name "Net-(U$9-NR)") (class "Default")
      (node (ref "C52") (pin "1") (pinfunction "1_1") (pintype "passive"))
      (node (ref "U$9") (pin "P$6") (pinfunction "NR_P$6") (pintype "bidirectional"))
    )
    (net (code "106") (name "Net-(U$10-IN)") (class "Default")
      (node (ref "U$10") (pin "8") (pinfunction "IN_8") (pintype "bidirectional"))
      (node (ref "U2") (pin "20") (pinfunction "PA_OUT_20") (pintype "output"))
    )
    (net (code "107") (name "Net-(U$10-OUT)") (class "Default")
      (node (ref "U$10") (pin "4") (pinfunction "OUT_4") (pintype "bidirectional"))
      (node (ref "U2") (pin "16") (pinfunction "TX_IN_16") (pintype "output"))
    )
    (net (code "108") (name "Net-(U1-SW)") (class "Default")
      (node (ref "L4") (pin "1") (pinfunction "1_1") (pintype "passive"))
      (node (ref "U1") (pin "2") (pinfunction "SW_2") (pintype "bidirectional"))
    )
    (net (code "109") (name "Net-(U2-ANT1)") (class "Default")
      (node (ref "C23") (pin "1") (pinfunction "1_1") (pintype "passive"))
      (node (ref "C25") (pin "1") (pinfunction "1_1") (pintype "passive"))
      (node (ref "L3") (pin "1") (pinfunction "1_1") (pintype "passive"))
      (node (ref "U2") (pin "14") (pinfunction "ANT1_14") (pintype "passive"))
    )
    (net (code "110") (name "Net-(U2-ANT2)") (class "Default")
      (node (ref "R37") (pin "1") (pinfunction "1_1") (pintype "passive"))
      (node (ref "U2") (pin "12") (pinfunction "ANT2_12") (pintype "passive"))
    )
    (net (code "111") (name "Net-(U2-CPS)") (class "Default")
      (node (ref "C55") (pin "2") (pinfunction "2_2") (pintype "passive"))
      (node (ref "R5") (pin "2") (pinfunction "2_2") (pintype "passive"))
      (node (ref "U2") (pin "3") (pinfunction "CPS_3") (pintype "input"))
    )
    (net (code "112") (name "Net-(U2-CSD)") (class "Default")
      (node (ref "C56") (pin "2") (pinfunction "2_2") (pintype "passive"))
      (node (ref "R46") (pin "2") (pinfunction "2_2") (pintype "passive"))
      (node (ref "U2") (pin "1") (pinfunction "CSD_1") (pintype "input"))
    )
    (net (code "113") (name "Net-(U2-CTX)") (class "Default")
      (node (ref "C36") (pin "2") (pinfunction "2_2") (pintype "passive"))
      (node (ref "R1") (pin "2") (pinfunction "2_2") (pintype "passive"))
      (node (ref "U2") (pin "4") (pinfunction "CTX_4") (pintype "input"))
    )
    (net (code "114") (name "Net-(U2-PA_IN)") (class "Default")
      (node (ref "C38") (pin "2") (pinfunction "2_2") (pintype "passive"))
      (node (ref "U2") (pin "2") (pinfunction "PA_IN_2") (pintype "input"))
    )
    (net (code "115") (name "Net-(U2-TR)") (class "Default")
      (node (ref "C2") (pin "1") (pinfunction "1_1") (pintype "passive"))
      (node (ref "U2") (pin "6") (pinfunction "TR_6") (pintype "bidirectional"))
    )
    (net (code "116") (name "Net-(U2-TX_FLT)") (class "Default")
      (node (ref "R19") (pin "2") (pinfunction "2_2") (pintype "passive"))
      (node (ref "U2") (pin "5") (pinfunction "TX_FLT_5") (pintype "passive"))
    )
    (net (code "117") (name "Net-(U2-VCC0)") (class "Default")
      (node (ref "C39") (pin "1") (pinfunction "1_1") (pintype "passive"))
      (node (ref "L7") (pin "1") (pinfunction "1_1") (pintype "passive"))
      (node (ref "U2") (pin "23") (pinfunction "VCC0_23") (pintype "power_in"))
    )
    (net (code "118") (name "Net-(U2-VCC1)") (class "Default")
      (node (ref "C44") (pin "1") (pinfunction "1_1") (pintype "passive"))
      (node (ref "L8") (pin "1") (pinfunction "1_1") (pintype "passive"))
      (node (ref "U2") (pin "24") (pinfunction "VCC1_24") (pintype "power_in"))
    )
    (net (code "119") (name "Net-(U2-VCC2)") (class "Default")
      (node (ref "L10") (pin "1") (pinfunction "1_1") (pintype "passive"))
      (node (ref "U2") (pin "21") (pinfunction "VCC2_21") (pintype "power_in"))
    )
    (net (code "120") (name "Net-(X3-ANT)") (class "Default")
      (node (ref "C37") (pin "2") (pinfunction "2_2") (pintype "passive"))
      (node (ref "X3") (pin "P") (pinfunction "ANT_P") (pintype "bidirectional"))
    )
    (net (code "121") (name "RX") (class "Default")
      (node (ref "L1") (pin "2") (pinfunction "2_2") (pintype "passive"))
      (node (ref "L2") (pin "1") (pinfunction "1_1") (pintype "passive"))
      (node (ref "U$2") (pin "27") (pinfunction "RF_IN_27") (pintype "bidirectional"))
      (node (ref "U$3") (pin "27") (pinfunction "RF_IN_27") (pintype "bidirectional"))
    )
    (net (code "122") (name "TX_N") (class "Default")
      (node (ref "U$2") (pin "29") (pinfunction "RF_ON_29") (pintype "bidirectional"))
      (node (ref "U13") (pin "P$6") (pinfunction "BALANCE_2_P$6") (pintype "bidirectional"))
    )
    (net (code "123") (name "TX_P") (class "Default")
      (node (ref "U$2") (pin "30") (pinfunction "RF_OP_30") (pintype "bidirectional"))
      (node (ref "U13") (pin "P$4") (pinfunction "BALANCE_1_P$4") (pintype "bidirectional"))
    )
    (net (code "124") (name "VCC_FEM") (class "Default")
      (node (ref "C54") (pin "1") (pinfunction "1_1") (pintype "passive"))
      (node (ref "L9") (pin "2") (pinfunction "2_2") (pintype "passive"))
      (node (ref "R38") (pin "2") (pinfunction "2_2") (pintype "passive"))
      (node (ref "R46") (pin "1") (pinfunction "1_1") (pintype "passive"))
      (node (ref "U$9") (pin "P$1") (pinfunction "OUT_P$1") (pintype "bidirectional"))
      (node (ref "U$9") (pin "P$2") (pinfunction "OUT_P$2") (pintype "bidirectional"))
    )
    (net (code "125") (name "unconnected-(GPS-ANT_ON-Pad13)") (class "Default")
      (node (ref "GPS") (pin "13") (pinfunction "ANT_ON_13") (pintype "bidirectional"))
    )
    (net (code "126") (name "unconnected-(GPS-EXTINT-Pad5)") (class "Default")
      (node (ref "GPS") (pin "5") (pinfunction "EXTINT_5") (pintype "bidirectional"))
    )
    (net (code "127") (name "unconnected-(GPS-REVD-Pad18)") (class "Default")
      (node (ref "GPS") (pin "18") (pinfunction "REVD_18") (pintype "bidirectional"))
    )
    (net (code "128") (name "unconnected-(GPS-SCL-Pad17)") (class "Default")
      (node (ref "GPS") (pin "17") (pinfunction "SCL_17") (pintype "bidirectional"))
    )
    (net (code "129") (name "unconnected-(GPS-SDA-Pad16)") (class "Default")
      (node (ref "GPS") (pin "16") (pinfunction "SDA_16") (pintype "bidirectional"))
    )
    (net (code "130") (name "unconnected-(GPS-V_ANT-Pad15)") (class "Default")
      (node (ref "GPS") (pin "15") (pinfunction "V_ANT_15") (pintype "bidirectional"))
    )
    (net (code "131") (name "unconnected-(U$1-LNA_B_CTRL-Pad27)") (class "Default")
      (node (ref "U$1") (pin "27") (pinfunction "LNA_B_CTRL_27") (pintype "bidirectional"))
    )
    (net (code "132") (name "unconnected-(U$1-PA_B_CTRL-Pad26)") (class "Default")
      (node (ref "U$1") (pin "26") (pinfunction "PA_B_CTRL_26") (pintype "bidirectional"))
    )
    (net (code "133") (name "unconnected-(U$1-PA_GAIN0-Pad18)") (class "Default")
      (node (ref "U$1") (pin "18") (pinfunction "PA_GAIN0_18") (pintype "bidirectional"))
    )
    (net (code "134") (name "unconnected-(U$1-PA_GAIN1-Pad17)") (class "Default")
      (node (ref "U$1") (pin "17") (pinfunction "PA_GAIN1_17") (pintype "bidirectional"))
    )
    (net (code "135") (name "unconnected-(U$1-RADIO_A_EN-Pad13)") (class "Default")
      (node (ref "U$1") (pin "13") (pinfunction "RADIO_A_EN_13") (pintype "bidirectional"))
    )
    (net (code "136") (name "unconnected-(U$1-RADIO_B_EN-Pad28)") (class "Default")
      (node (ref "U$1") (pin "28") (pinfunction "RADIO_B_EN_28") (pintype "bidirectional"))
    )
    (net (code "137") (name "unconnected-(U$2-DIO0-Pad21)") (class "Default")
      (node (ref "U$2") (pin "21") (pinfunction "DIO0_21") (pintype "bidirectional"))
    )
    (net (code "138") (name "unconnected-(U$2-DIO1-Pad22)") (class "Default")
      (node (ref "U$2") (pin "22") (pinfunction "DIO1_22") (pintype "bidirectional"))
    )
    (net (code "139") (name "unconnected-(U$2-DIO2-Pad23)") (class "Default")
      (node (ref "U$2") (pin "23") (pinfunction "DIO2_23") (pintype "bidirectional"))
    )
    (net (code "140") (name "unconnected-(U$2-DIO3-Pad24)") (class "Default")
      (node (ref "U$2") (pin "24") (pinfunction "DIO3_24") (pintype "bidirectional"))
    )
    (net (code "141") (name "unconnected-(U$2-XTA-Pad6)") (class "Default")
      (node (ref "U$2") (pin "6") (pinfunction "XTA_6") (pintype "bidirectional"))
    )
    (net (code "142") (name "unconnected-(U$3-CLK_IN-Pad11)") (class "Default")
      (node (ref "U$3") (pin "11") (pinfunction "CLK_IN_11") (pintype "bidirectional"))
    )
    (net (code "143") (name "unconnected-(U$3-DIO0-Pad21)") (class "Default")
      (node (ref "U$3") (pin "21") (pinfunction "DIO0_21") (pintype "bidirectional"))
    )
    (net (code "144") (name "unconnected-(U$3-DIO1-Pad22)") (class "Default")
      (node (ref "U$3") (pin "22") (pinfunction "DIO1_22") (pintype "bidirectional"))
    )
    (net (code "145") (name "unconnected-(U$3-DIO2-Pad23)") (class "Default")
      (node (ref "U$3") (pin "23") (pinfunction "DIO2_23") (pintype "bidirectional"))
    )
    (net (code "146") (name "unconnected-(U$3-DIO3-Pad24)") (class "Default")
      (node (ref "U$3") (pin "24") (pinfunction "DIO3_24") (pintype "bidirectional"))
    )
    (net (code "147") (name "unconnected-(U$3-RF_ON-Pad29)") (class "Default")
      (node (ref "U$3") (pin "29") (pinfunction "RF_ON_29") (pintype "bidirectional"))
    )
    (net (code "148") (name "unconnected-(U$3-RF_OP-Pad30)") (class "Default")
      (node (ref "U$3") (pin "30") (pinfunction "RF_OP_30") (pintype "bidirectional"))
    )
    (net (code "149") (name "unconnected-(U$3-XTA-Pad6)") (class "Default")
      (node (ref "U$3") (pin "6") (pinfunction "XTA_6") (pintype "bidirectional"))
    )
    (net (code "150") (name "unconnected-(U$5-GEN4{slash}GPIO23-Pad16)") (class "Default")
      (node (ref "U$5") (pin "16") (pinfunction "GEN4/GPIO23_16") (pintype "bidirectional"))
    )
    (net (code "151") (name "unconnected-(U$5-GPIO2{slash}SDA1-Pad3)") (class "Default")
      (node (ref "U$5") (pin "3") (pinfunction "GPIO2/SDA1_3") (pintype "bidirectional"))
    )
    (net (code "152") (name "unconnected-(U$5-GPIO3{slash}SCL1-Pad5)") (class "Default")
      (node (ref "U$5") (pin "5") (pinfunction "GPIO3/SCL1_5") (pintype "bidirectional"))
    )
    (net (code "153") (name "unconnected-(U$5-GPIO4{slash}GCKL-Pad7)") (class "Default")
      (node (ref "U$5") (pin "7") (pinfunction "GPIO4/GCKL_7") (pintype "bidirectional"))
    )
    (net (code "154") (name "unconnected-(U$5-GPIO5-Pad29)") (class "Default")
      (node (ref "U$5") (pin "29") (pinfunction "GPIO5_29") (pintype "bidirectional"))
    )
    (net (code "155") (name "unconnected-(U$5-GPIO6-Pad31)") (class "Default")
      (node (ref "U$5") (pin "31") (pinfunction "GPIO6_31") (pintype "bidirectional"))
    )
    (net (code "156") (name "unconnected-(U$5-GPIO12-Pad32)") (class "Default")
      (node (ref "U$5") (pin "32") (pinfunction "GPIO12_32") (pintype "bidirectional"))
    )
    (net (code "157") (name "unconnected-(U$5-GPIO13-Pad33)") (class "Default")
      (node (ref "U$5") (pin "33") (pinfunction "GPIO13_33") (pintype "bidirectional"))
    )
    (net (code "158") (name "unconnected-(U$5-GPIO16-Pad36)") (class "Default")
      (node (ref "U$5") (pin "36") (pinfunction "GPIO16_36") (pintype "bidirectional"))
    )
    (net (code "159") (name "unconnected-(U$5-GPIO17{slash}GEN0-Pad11)") (class "Default")
      (node (ref "U$5") (pin "11") (pinfunction "GPIO17/GEN0_11") (pintype "bidirectional"))
    )
    (net (code "160") (name "unconnected-(U$5-GPIO18-Pad12)") (class "Default")
      (node (ref "U$5") (pin "12") (pinfunction "GPIO18_12") (pintype "bidirectional"))
    )
    (net (code "161") (name "unconnected-(U$5-GPIO19-Pad35)") (class "Default")
      (node (ref "U$5") (pin "35") (pinfunction "GPIO19_35") (pintype "bidirectional"))
    )
    (net (code "162") (name "unconnected-(U$5-GPIO20-Pad38)") (class "Default")
      (node (ref "U$5") (pin "38") (pinfunction "GPIO20_38") (pintype "bidirectional"))
    )
    (net (code "163") (name "unconnected-(U$5-GPIO22{slash}GEN3-Pad15)") (class "Default")
      (node (ref "U$5") (pin "15") (pinfunction "GPIO22/GEN3_15") (pintype "bidirectional"))
    )
    (net (code "164") (name "unconnected-(U$5-GPIO26-Pad37)") (class "Default")
      (node (ref "U$5") (pin "37") (pinfunction "GPIO26_37") (pintype "bidirectional"))
    )
    (net (code "165") (name "unconnected-(U$5-GPIO27{slash}GEN2-Pad13)") (class "Default")
      (node (ref "U$5") (pin "13") (pinfunction "GPIO27/GEN2_13") (pintype "bidirectional"))
    )
    (net (code "166") (name "unconnected-(U$5-ID_SC-Pad28)") (class "Default")
      (node (ref "U$5") (pin "28") (pinfunction "ID_SC_28") (pintype "bidirectional"))
    )
    (net (code "167") (name "unconnected-(U$5-ID_SD-Pad27)") (class "Default")
      (node (ref "U$5") (pin "27") (pinfunction "ID_SD_27") (pintype "bidirectional"))
    )
    (net (code "168") (name "unconnected-(U$5-~{CE}{slash}GPIO7-Pad26)") (class "Default")
      (node (ref "U$5") (pin "26") (pinfunction "~{CE}/GPIO7_26") (pintype "bidirectional"))
    )
    (net (code "169") (name "unconnected-(U$6-PG-PadP$3)") (class "Default")
      (node (ref "U$6") (pin "P$3") (pinfunction "PG_P$3") (pintype "bidirectional"))
    )
  )
)
